# Sheet1.net
KiCad netlist of a schematic drawn in Altium Designer
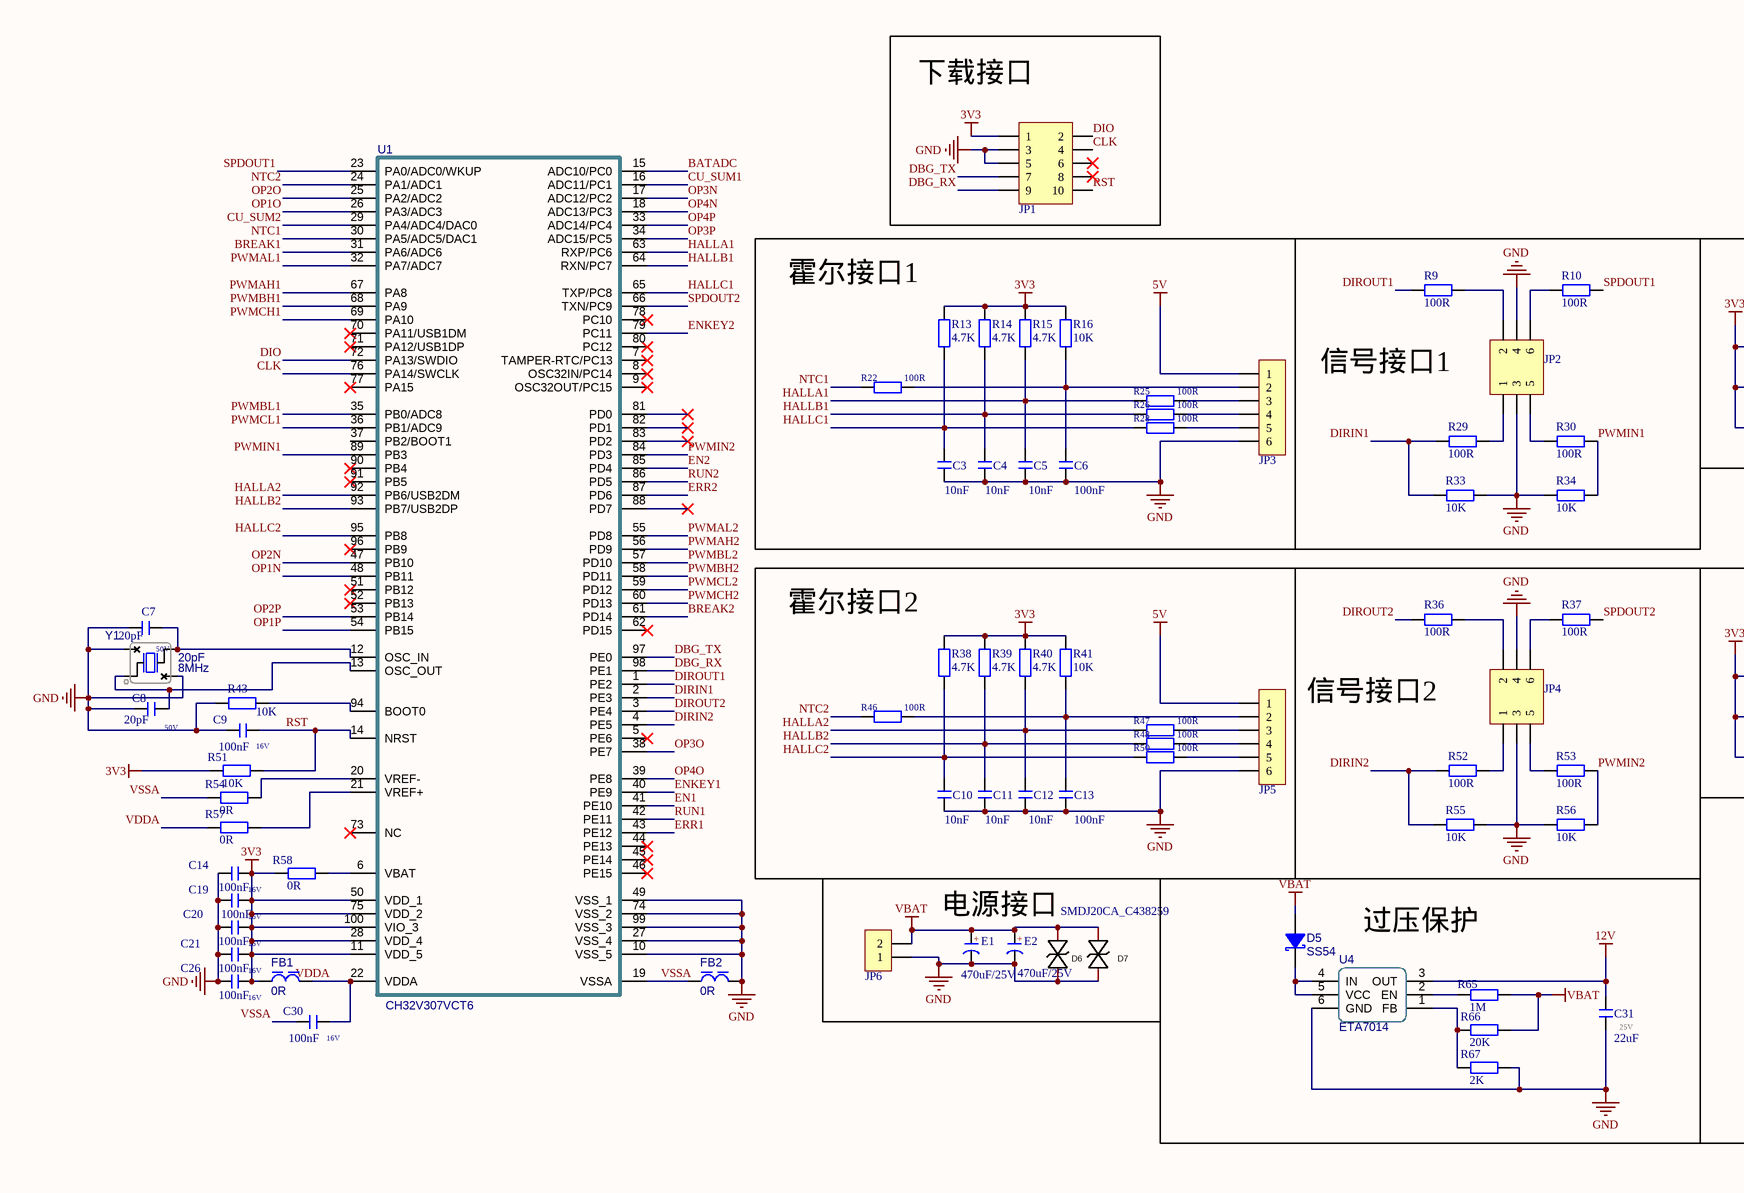
[diagram p0: Sheet1.SchDoc, top left]
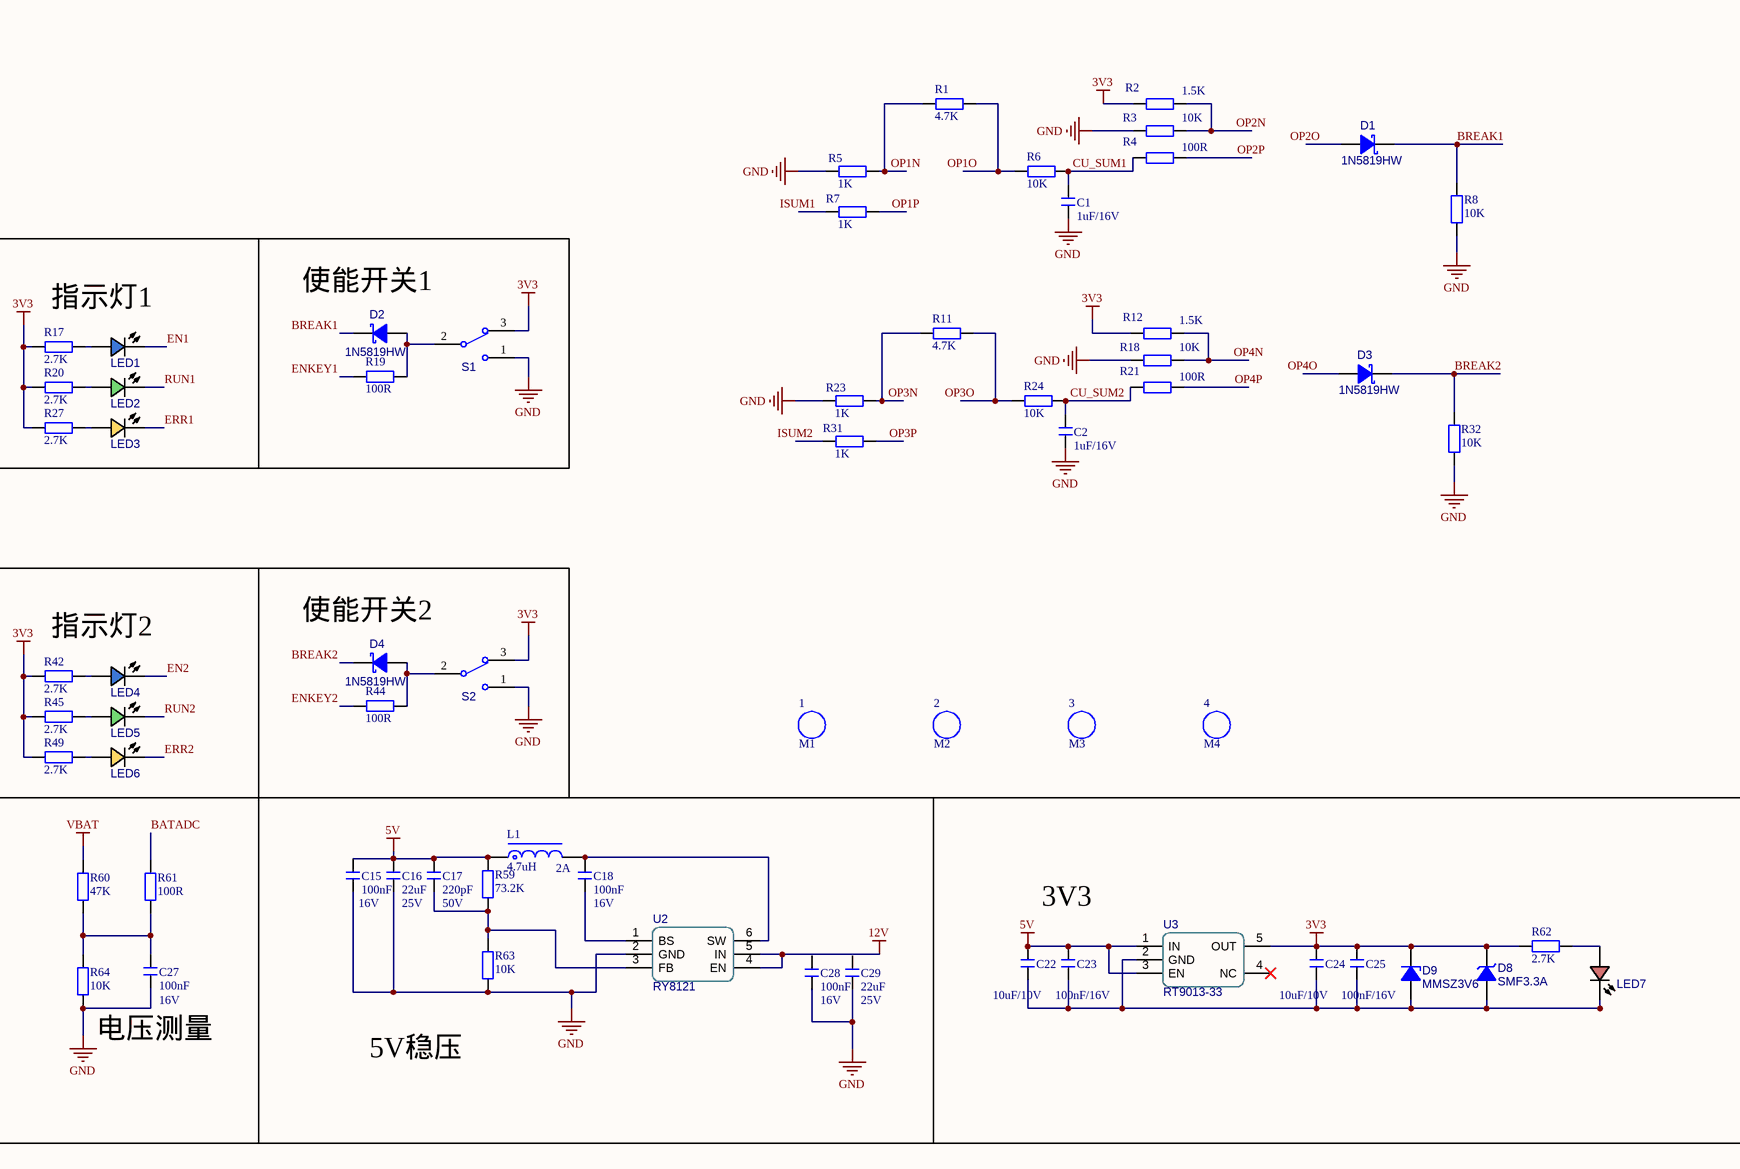
[diagram p1: Sheet1.SchDoc, top right]
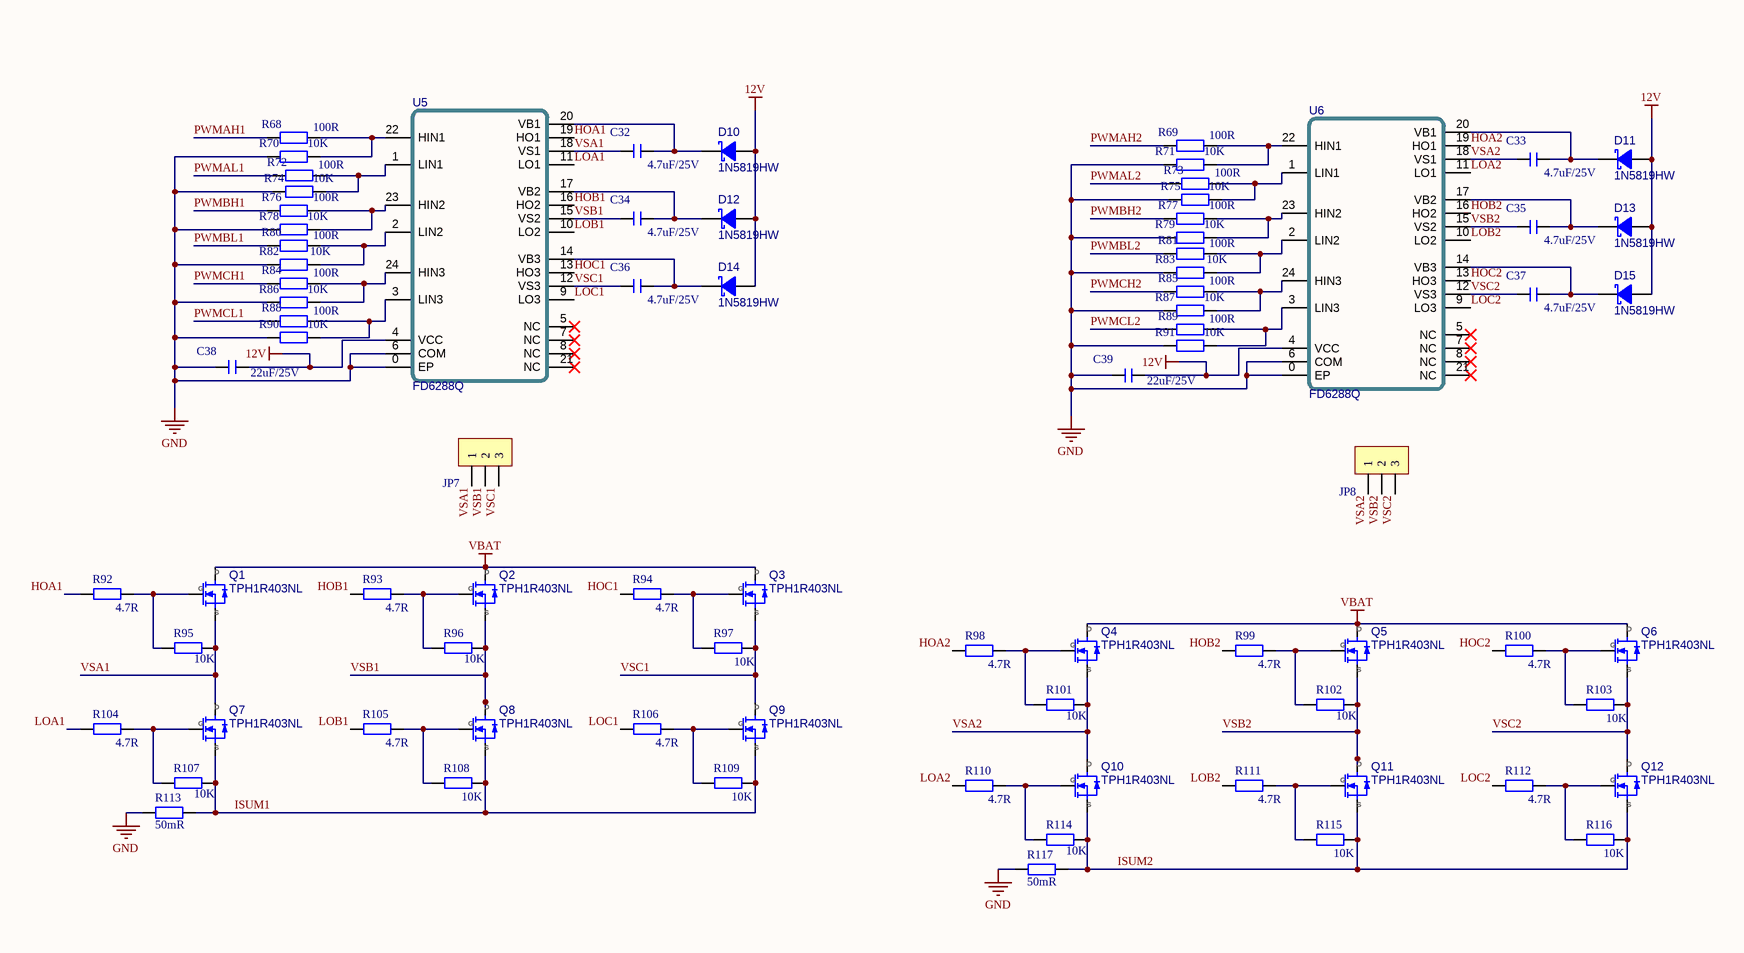
[diagram p2: Sheet1.SchDoc, bottom left]

(export (version "E")
  (design (tool "Eeschema 10.0.6"))
  (components
    (comp (ref "1")
      (value "M1")
      (footprint "M3 125X200")
      (description "铜柱孔")
      (fields (field (name "版权归属") "源创客"))
      (libsource (lib "15.1 - 未分类器件") (part "M3"))
    )
    (comp (ref "2")
      (value "M2")
      (footprint "M3 125X200")
      (description "铜柱孔")
      (fields (field (name "版权归属") "源创客"))
      (libsource (lib "15.1 - 未分类器件") (part "M3"))
    )
    (comp (ref "3")
      (value "M3")
      (footprint "M3 125X200")
      (description "铜柱孔")
      (fields (field (name "版权归属") "源创客"))
      (libsource (lib "15.1 - 未分类器件") (part "M3"))
    )
    (comp (ref "4")
      (value "M4")
      (footprint "M3 125X200")
      (description "铜柱孔")
      (fields (field (name "版权归属") "源创客"))
      (libsource (lib "15.1 - 未分类器件") (part "M3"))
    )
    (comp (ref "C1")
      (value "1uF/16V")
      (footprint "C 0603_L")
      (description "无极性贴片电容")
      (fields (field (name "版权归属") "源创客"))
      (libsource (lib "3.1   - 电阻-电容-电感") (part "C"))
    )
    (comp (ref "C2")
      (value "1uF/16V")
      (footprint "C 0603_L")
      (description "无极性贴片电容")
      (fields (field (name "版权归属") "源创客"))
      (libsource (lib "3.1   - 电阻-电容-电感") (part "C"))
    )
    (comp (ref "C3")
      (value "10nF")
      (footprint "C 0402_L")
      (description "无极性贴片电容")
      (fields (field (name "版权归属") "源创客"))
      (libsource (lib "3.1   - 电阻-电容-电感") (part "C"))
    )
    (comp (ref "C4")
      (value "10nF")
      (footprint "C 0402_L")
      (description "无极性贴片电容")
      (fields (field (name "版权归属") "源创客"))
      (libsource (lib "3.1   - 电阻-电容-电感") (part "C"))
    )
    (comp (ref "C5")
      (value "10nF")
      (footprint "C 0402_L")
      (description "无极性贴片电容")
      (fields (field (name "版权归属") "源创客"))
      (libsource (lib "3.1   - 电阻-电容-电感") (part "C"))
    )
    (comp (ref "C6")
      (value "100nF")
      (footprint "C 0402_L")
      (description "无极性贴片电容")
      (fields (field (name "版权归属") "源创客"))
      (libsource (lib "3.1   - 电阻-电容-电感") (part "C"))
    )
    (comp (ref "C7")
      (value "20pF")
      (footprint "C 0402_L")
      (description "无极性贴片电容")
      (fields (field (name "电压") "50V") (field (name "版权归属") "源创客"))
      (libsource (lib "3.1   - 电阻-电容-电感") (part "C"))
    )
    (comp (ref "C8")
      (value "20pF")
      (footprint "C 0402_L")
      (description "无极性贴片电容")
      (fields (field (name "电压") "50V") (field (name "版权归属") "源创客"))
      (libsource (lib "3.1   - 电阻-电容-电感") (part "C"))
    )
    (comp (ref "C9")
      (value "100nF")
      (footprint "C 0402_L")
      (description "无极性贴片电容")
      (fields (field (name "电压") "16V") (field (name "版权归属") "源创客"))
      (libsource (lib "3.1   - 电阻-电容-电感") (part "C"))
    )
    (comp (ref "C10")
      (value "10nF")
      (footprint "C 0402_L")
      (description "无极性贴片电容")
      (fields (field (name "版权归属") "源创客"))
      (libsource (lib "3.1   - 电阻-电容-电感") (part "C"))
    )
    (comp (ref "C11")
      (value "10nF")
      (footprint "C 0402_L")
      (description "无极性贴片电容")
      (fields (field (name "版权归属") "源创客"))
      (libsource (lib "3.1   - 电阻-电容-电感") (part "C"))
    )
    (comp (ref "C12")
      (value "10nF")
      (footprint "C 0402_L")
      (description "无极性贴片电容")
      (fields (field (name "版权归属") "源创客"))
      (libsource (lib "3.1   - 电阻-电容-电感") (part "C"))
    )
    (comp (ref "C13")
      (value "100nF")
      (footprint "C 0402_L")
      (description "无极性贴片电容")
      (fields (field (name "版权归属") "源创客"))
      (libsource (lib "3.1   - 电阻-电容-电感") (part "C"))
    )
    (comp (ref "C14")
      (value "100nF")
      (footprint "C 0402_L")
      (description "无极性贴片电容")
      (fields (field (name "电压") "16V") (field (name "版权归属") "源创客"))
      (libsource (lib "3.1   - 电阻-电容-电感") (part "C"))
    )
    (comp (ref "C15")
      (value "100nF")
      (footprint "C 0402_L")
      (description "无极性贴片电容")
      (fields (field (name "V") "16V") (field (name "版权归属") "源创客"))
      (libsource (lib "3.1   - 电阻-电容-电感") (part "C"))
    )
    (comp (ref "C16")
      (value "22uF")
      (footprint "C 0805_L")
      (description "无极性贴片电容")
      (fields (field (name "V") "25V") (field (name "版权归属") "源创客"))
      (libsource (lib "3.1   - 电阻-电容-电感") (part "C"))
    )
    (comp (ref "C17")
      (value "220pF")
      (footprint "C 0402_L")
      (description "无极性贴片电容")
      (fields (field (name "V") "50V") (field (name "版权归属") "源创客"))
      (libsource (lib "3.1   - 电阻-电容-电感") (part "C"))
    )
    (comp (ref "C18")
      (value "100nF")
      (footprint "C 0402_L")
      (description "无极性贴片电容")
      (fields (field (name "V") "16V") (field (name "版权归属") "源创客"))
      (libsource (lib "3.1   - 电阻-电容-电感") (part "C"))
    )
    (comp (ref "C19")
      (value "100nF")
      (footprint "C 0402_L")
      (description "无极性贴片电容")
      (fields (field (name "电压") "16V") (field (name "版权归属") "源创客"))
      (libsource (lib "3.1   - 电阻-电容-电感") (part "C"))
    )
    (comp (ref "C20")
      (value "100nF")
      (footprint "C 0402_L")
      (description "无极性贴片电容")
      (fields (field (name "电压") "16V") (field (name "版权归属") "源创客"))
      (libsource (lib "3.1   - 电阻-电容-电感") (part "C"))
    )
    (comp (ref "C21")
      (value "100nF")
      (footprint "C 0402_L")
      (description "无极性贴片电容")
      (fields (field (name "电压") "16V") (field (name "版权归属") "源创客"))
      (libsource (lib "3.1   - 电阻-电容-电感") (part "C"))
    )
    (comp (ref "C22")
      (value "10uF/10V")
      (footprint "C 0603_L")
      (description "无极性贴片电容")
      (fields (field (name "版权归属") "源创客"))
      (libsource (lib "3.1   - 电阻-电容-电感") (part "C"))
    )
    (comp (ref "C23")
      (value "100nF/16V")
      (footprint "C 0402_L")
      (description "无极性贴片电容")
      (fields (field (name "版权归属") "源创客"))
      (libsource (lib "3.1   - 电阻-电容-电感") (part "C"))
    )
    (comp (ref "C24")
      (value "10uF/10V")
      (footprint "C 0603_L")
      (description "无极性贴片电容")
      (fields (field (name "版权归属") "源创客"))
      (libsource (lib "3.1   - 电阻-电容-电感") (part "C"))
    )
    (comp (ref "C25")
      (value "100nF/16V")
      (footprint "C 0402_L")
      (description "无极性贴片电容")
      (fields (field (name "版权归属") "源创客"))
      (libsource (lib "3.1   - 电阻-电容-电感") (part "C"))
    )
    (comp (ref "C26")
      (value "100nF")
      (footprint "C 0402_L")
      (description "无极性贴片电容")
      (fields (field (name "电压") "16V") (field (name "版权归属") "源创客"))
      (libsource (lib "3.1   - 电阻-电容-电感") (part "C"))
    )
    (comp (ref "C27")
      (value "100nF")
      (footprint "C 0402_L")
      (description "无极性贴片电容")
      (fields (field (name "V") "16V") (field (name "版权归属") "源创客"))
      (libsource (lib "3.1   - 电阻-电容-电感") (part "C"))
    )
    (comp (ref "C28")
      (value "100nF")
      (footprint "C 0402_L")
      (description "无极性贴片电容")
      (fields (field (name "V") "16V") (field (name "版权归属") "源创客"))
      (libsource (lib "3.1   - 电阻-电容-电感") (part "C"))
    )
    (comp (ref "C29")
      (value "22uF")
      (footprint "C 0805_L")
      (description "无极性贴片电容")
      (fields (field (name "V") "25V") (field (name "版权归属") "源创客"))
      (libsource (lib "3.1   - 电阻-电容-电感") (part "C"))
    )
    (comp (ref "C30")
      (value "100nF")
      (footprint "C 0402_M")
      (description "无极性贴片电容")
      (fields (field (name "电压") "16V") (field (name "版权归属") "源创客"))
      (libsource (lib "3.1   - 电阻-电容-电感") (part "C"))
    )
    (comp (ref "C31")
      (value "22uF")
      (footprint "C 0805_L")
      (description "无极性贴片电容")
      (fields (field (name "V") "25V") (field (name "版权归属") "源创客"))
      (libsource (lib "3.1   - 电阻-电容-电感") (part "C"))
    )
    (comp (ref "C32")
      (value "4.7uF/25V")
      (footprint "C 0805_L")
      (description "无极性贴片电容")
      (fields (field (name "版权归属") "源创客"))
      (libsource (lib "3.1   - 电阻-电容-电感") (part "C"))
    )
    (comp (ref "C33")
      (value "4.7uF/25V")
      (footprint "C 0805_L")
      (description "无极性贴片电容")
      (fields (field (name "版权归属") "源创客"))
      (libsource (lib "3.1   - 电阻-电容-电感") (part "C"))
    )
    (comp (ref "C34")
      (value "4.7uF/25V")
      (footprint "C 0805_L")
      (description "无极性贴片电容")
      (fields (field (name "版权归属") "源创客"))
      (libsource (lib "3.1   - 电阻-电容-电感") (part "C"))
    )
    (comp (ref "C35")
      (value "4.7uF/25V")
      (footprint "C 0805_L")
      (description "无极性贴片电容")
      (fields (field (name "版权归属") "源创客"))
      (libsource (lib "3.1   - 电阻-电容-电感") (part "C"))
    )
    (comp (ref "C36")
      (value "4.7uF/25V")
      (footprint "C 0805_L")
      (description "无极性贴片电容")
      (fields (field (name "版权归属") "源创客"))
      (libsource (lib "3.1   - 电阻-电容-电感") (part "C"))
    )
    (comp (ref "C37")
      (value "4.7uF/25V")
      (footprint "C 0805_L")
      (description "无极性贴片电容")
      (fields (field (name "版权归属") "源创客"))
      (libsource (lib "3.1   - 电阻-电容-电感") (part "C"))
    )
    (comp (ref "C38")
      (value "22uF/25V")
      (footprint "C 0805_L")
      (description "无极性贴片电容")
      (fields (field (name "版权归属") "源创客"))
      (libsource (lib "3.1   - 电阻-电容-电感") (part "C"))
    )
    (comp (ref "C39")
      (value "22uF/25V")
      (footprint "C 0805_L")
      (description "无极性贴片电容")
      (fields (field (name "版权归属") "源创客"))
      (libsource (lib "3.1   - 电阻-电容-电感") (part "C"))
    )
    (comp (ref "D1")
      (value "1N5819HW")
      (footprint "SOD-123-L")
      (description "1N5819HW 肖特基二极管")
      (libsource (lib "无刷驱动_CH32V307_V1.0") (part "1N5819HW"))
    )
    (comp (ref "D2")
      (value "1N5819HW")
      (footprint "SOD-123-L")
      (description "1N5819HW 肖特基二极管")
      (libsource (lib "无刷驱动_CH32V307_V1.0") (part "1N5819HW"))
    )
    (comp (ref "D3")
      (value "1N5819HW")
      (footprint "SOD-123-L")
      (description "1N5819HW 肖特基二极管")
      (libsource (lib "无刷驱动_CH32V307_V1.0") (part "1N5819HW"))
    )
    (comp (ref "D4")
      (value "1N5819HW")
      (footprint "SOD-123-L")
      (description "1N5819HW 肖特基二极管")
      (libsource (lib "无刷驱动_CH32V307_V1.0") (part "1N5819HW"))
    )
    (comp (ref "D5")
      (value "SS54")
      (footprint "SMA-L[DO-214AC]")
      (description "SS54 肖特基二极管")
      (libsource (lib "无刷驱动_CH32V307_V1.0") (part "SS54"))
    )
    (comp (ref "D6")
      (value "SMDJ20CA_C438259")
      (footprint "SMC_L6.9-W5.9-LS7.9-BI")
      (fields (field (name "DESIGNER") "U?"))
      (libsource (lib "SMDJ20CA_C4382591_SMDJ20CA_C438259") (part "SMDJ20CA_C438259"))
    )
    (comp (ref "D7")
      (value "SMDJ20CA_C438259")
      (footprint "SMC_L6.9-W5.9-LS7.9-BI")
      (fields (field (name "DESIGNER") "U?"))
      (libsource (lib "SMDJ20CA_C4382591_SMDJ20CA_C438259") (part "SMDJ20CA_C438259"))
    )
    (comp (ref "D8")
      (value "SMF3.3A")
      (footprint "SOD-123-L")
      (description "TRANSIENT VOLTAGE  SUPPRESSOR DIODE")
      (fields (field (name "PUBLISHER") "Altium Limited"))
      (libsource (lib "无刷驱动_CH32V307_V1.0") (part "Diode TVS Uni-Dir"))
    )
    (comp (ref "D9")
      (value "MMSZ3V6")
      (footprint "SOD-123-L")
      (description "稳压二极管 齐纳二极管  Zener Diode")
      (fields (field (name "PUBLISHER") "Altium Limited"))
      (libsource (lib "无刷驱动_CH32V307_V1.0") (part "Diode Zen"))
    )
    (comp (ref "D10")
      (value "1N5819HW")
      (footprint "SOD-123-L")
      (description "1N5819HW 肖特基二极管")
      (libsource (lib "无刷驱动_CH32V307_V1.0") (part "1N5819HW"))
    )
    (comp (ref "D11")
      (value "1N5819HW")
      (footprint "SOD-123-L")
      (description "1N5819HW 肖特基二极管")
      (libsource (lib "无刷驱动_CH32V307_V1.0") (part "1N5819HW"))
    )
    (comp (ref "D12")
      (value "1N5819HW")
      (footprint "SOD-123-L")
      (description "1N5819HW 肖特基二极管")
      (libsource (lib "无刷驱动_CH32V307_V1.0") (part "1N5819HW"))
    )
    (comp (ref "D13")
      (value "1N5819HW")
      (footprint "SOD-123-L")
      (description "1N5819HW 肖特基二极管")
      (libsource (lib "无刷驱动_CH32V307_V1.0") (part "1N5819HW"))
    )
    (comp (ref "D14")
      (value "1N5819HW")
      (footprint "SOD-123-L")
      (description "1N5819HW 肖特基二极管")
      (libsource (lib "无刷驱动_CH32V307_V1.0") (part "1N5819HW"))
    )
    (comp (ref "D15")
      (value "1N5819HW")
      (footprint "SOD-123-L")
      (description "1N5819HW 肖特基二极管")
      (libsource (lib "无刷驱动_CH32V307_V1.0") (part "1N5819HW"))
    )
    (comp (ref "E1")
      (value "470uF/25V")
      (footprint "CAP 5.0*10*12.5")
      (description "直插电解电容")
      (fields (field (name "版权归属") "源创客"))
      (libsource (lib "3.1   - 电阻-电容-电感") (part "C-CAP"))
    )
    (comp (ref "E2")
      (value "470uF/25V")
      (footprint "CAP 5.0*10*16")
      (description "直插电解电容")
      (fields (field (name "版权归属") "源创客"))
      (libsource (lib "3.1   - 电阻-电容-电感") (part "C-CAP"))
    )
    (comp (ref "FB1")
      (value "0R")
      (footprint "INDC1005[0402]S")
      (description "贴片磁珠")
      (fields (field (name "Comment") "0R @100MHz 500mA"))
      (libsource (lib "无刷驱动_CH32V307_V1.0") (part "FB-Chip"))
    )
    (comp (ref "FB2")
      (value "0R")
      (footprint "INDC1005[0402]S")
      (description "贴片磁珠")
      (fields (field (name "Comment") "0R @100MHz 500mA"))
      (libsource (lib "无刷驱动_CH32V307_V1.0") (part "FB-Chip"))
    )
    (comp (ref "JP1")
      (value "Header 5X2")
      (footprint "HDR2.54-WI-2x5P")
      (description "5*2P接插件")
      (fields (field (name "版权归属") "源创客"))
      (libsource (lib "4.5   - 接插件-脚距2.54") (part "Header 5X2"))
    )
    (comp (ref "JP2")
      (value "Header3X2")
      (footprint "HDR2.54-LI-2x3P")
      (description "3*2P接插件")
      (fields (field (name "版权归属") "源创客"))
      (libsource (lib "4.5   - 接插件-脚距2.54") (part "Header 3X2"))
    )
    (comp (ref "JP3")
      (value "HDR-1X6")
      (footprint "ZH1.5-WI-6P")
      (description "6P接插件")
      (fields (field (name "版权归属") "源创客"))
      (libsource (lib "4.3   - 接插件-脚距1.5") (part "Header 6"))
    )
    (comp (ref "JP4")
      (value "Header3X2")
      (footprint "HDR2.54-LI-2x3P")
      (description "3*2P接插件")
      (fields (field (name "版权归属") "源创客"))
      (libsource (lib "4.5   - 接插件-脚距2.54") (part "Header 3X2"))
    )
    (comp (ref "JP5")
      (value "HDR-1X6")
      (footprint "ZH1.5-WI-6P")
      (description "6P接插件")
      (fields (field (name "版权归属") "源创客"))
      (libsource (lib "4.3   - 接插件-脚距1.5") (part "Header 6"))
    )
    (comp (ref "JP6")
      (value "HDR-1X2")
      (footprint "KF350-2P")
      (description "2P接插件")
      (fields (field (name "版权归属") "源创客"))
      (libsource (lib "4.6   - 接插件-脚距3.5") (part "Header 2"))
    )
    (comp (ref "JP7")
      (value "HDR-1X3")
      (footprint "KF350-3P")
      (description "3P接插件")
      (fields (field (name "版权归属") "源创客"))
      (libsource (lib "4.6   - 接插件-脚距3.5") (part "Header 3"))
    )
    (comp (ref "JP8")
      (value "HDR-1X3")
      (footprint "KF350-3P")
      (description "3P接插件")
      (fields (field (name "版权归属") "源创客"))
      (libsource (lib "4.6   - 接插件-脚距3.5") (part "Header 3"))
    )
    (comp (ref "L1")
      (value "4.7uH")
      (footprint "CD31")
      (description "贴片功率电感")
      (fields (field (name "A") "2A") (field (name "版权归属") "源创客"))
      (libsource (lib "3.1   - 电阻-电容-电感") (part "L-CD"))
    )
    (comp (ref "LED1")
      (value "蓝色贴片LED")
      (footprint "LEDC1608(0603)-L")
      (fields (field (name "PUBLISHER") "Altium Limited"))
      (libsource (lib "无刷驱动_CH32V307_V1.0") (part "LED Chip Blue"))
    )
    (comp (ref "LED2")
      (value "翠绿贴片LED")
      (footprint "LEDC1608(0603)-L")
      (fields (field (name "PUBLISHER") "Altium Limited"))
      (libsource (lib "无刷驱动_CH32V307_V1.0") (part "LED Chip Green"))
    )
    (comp (ref "LED3")
      (value "黄色贴片LED")
      (footprint "LEDC1608(0603)-L")
      (fields (field (name "PUBLISHER") "Altium Limited"))
      (libsource (lib "无刷驱动_CH32V307_V1.0") (part "LED Chip Yellow"))
    )
    (comp (ref "LED4")
      (value "蓝色贴片LED")
      (footprint "LEDC1608(0603)-L")
      (fields (field (name "PUBLISHER") "Altium Limited"))
      (libsource (lib "无刷驱动_CH32V307_V1.0") (part "LED Chip Blue"))
    )
    (comp (ref "LED5")
      (value "翠绿贴片LED")
      (footprint "LEDC1608(0603)-L")
      (fields (field (name "PUBLISHER") "Altium Limited"))
      (libsource (lib "无刷驱动_CH32V307_V1.0") (part "LED Chip Green"))
    )
    (comp (ref "LED6")
      (value "黄色贴片LED")
      (footprint "LEDC1608(0603)-L")
      (fields (field (name "PUBLISHER") "Altium Limited"))
      (libsource (lib "无刷驱动_CH32V307_V1.0") (part "LED Chip Yellow"))
    )
    (comp (ref "LED7")
      (value "红色贴片LED")
      (footprint "LEDC1608(0603)-L")
      (fields (field (name "PUBLISHER") "Altium Limited"))
      (libsource (lib "无刷驱动_CH32V307_V1.0") (part "LED Chip Red"))
    )
    (comp (ref "Q1")
      (value "TPH1R403NL")
      (footprint "DFN5x6")
      (description "东芝 N沟 MOS")
      (libsource (lib "无刷驱动_CH32V307_V1.0") (part "TPH1R403NL"))
    )
    (comp (ref "Q2")
      (value "TPH1R403NL")
      (footprint "DFN5x6")
      (description "东芝 N沟 MOS")
      (libsource (lib "无刷驱动_CH32V307_V1.0") (part "TPH1R403NL"))
    )
    (comp (ref "Q3")
      (value "TPH1R403NL")
      (footprint "DFN5x6")
      (description "东芝 N沟 MOS")
      (libsource (lib "无刷驱动_CH32V307_V1.0") (part "TPH1R403NL"))
    )
    (comp (ref "Q4")
      (value "TPH1R403NL")
      (footprint "DFN5x6")
      (description "东芝 N沟 MOS")
      (libsource (lib "无刷驱动_CH32V307_V1.0") (part "TPH1R403NL"))
    )
    (comp (ref "Q5")
      (value "TPH1R403NL")
      (footprint "DFN5x6")
      (description "东芝 N沟 MOS")
      (libsource (lib "无刷驱动_CH32V307_V1.0") (part "TPH1R403NL"))
    )
    (comp (ref "Q6")
      (value "TPH1R403NL")
      (footprint "DFN5x6")
      (description "东芝 N沟 MOS")
      (libsource (lib "无刷驱动_CH32V307_V1.0") (part "TPH1R403NL"))
    )
    (comp (ref "Q7")
      (value "TPH1R403NL")
      (footprint "DFN5x6")
      (description "东芝 N沟 MOS")
      (libsource (lib "无刷驱动_CH32V307_V1.0") (part "TPH1R403NL"))
    )
    (comp (ref "Q8")
      (value "TPH1R403NL")
      (footprint "DFN5x6")
      (description "东芝 N沟 MOS")
      (libsource (lib "无刷驱动_CH32V307_V1.0") (part "TPH1R403NL"))
    )
    (comp (ref "Q9")
      (value "TPH1R403NL")
      (footprint "DFN5x6")
      (description "东芝 N沟 MOS")
      (libsource (lib "无刷驱动_CH32V307_V1.0") (part "TPH1R403NL"))
    )
    (comp (ref "Q10")
      (value "TPH1R403NL")
      (footprint "DFN5x6")
      (description "东芝 N沟 MOS")
      (libsource (lib "无刷驱动_CH32V307_V1.0") (part "TPH1R403NL"))
    )
    (comp (ref "Q11")
      (value "TPH1R403NL")
      (footprint "DFN5x6")
      (description "东芝 N沟 MOS")
      (libsource (lib "无刷驱动_CH32V307_V1.0") (part "TPH1R403NL"))
    )
    (comp (ref "Q12")
      (value "TPH1R403NL")
      (footprint "DFN5x6")
      (description "东芝 N沟 MOS")
      (libsource (lib "无刷驱动_CH32V307_V1.0") (part "TPH1R403NL"))
    )
    (comp (ref "R1")
      (value "4.7K")
      (footprint "R 0603_L")
      (description "贴片电阻")
      (fields (field (name "版权归属") "源创客"))
      (libsource (lib "3.1   - 电阻-电容-电感") (part "R"))
    )
    (comp (ref "R2")
      (value "1.5K")
      (footprint "R 0603_L")
      (description "贴片电阻")
      (fields (field (name "版权归属") "源创客"))
      (libsource (lib "3.1   - 电阻-电容-电感") (part "R"))
    )
    (comp (ref "R3")
      (value "10K")
      (footprint "R 0603_L")
      (description "贴片电阻")
      (fields (field (name "版权归属") "源创客"))
      (libsource (lib "3.1   - 电阻-电容-电感") (part "R"))
    )
    (comp (ref "R4")
      (value "100R")
      (footprint "R 0603_L")
      (description "贴片电阻")
      (fields (field (name "版权归属") "源创客"))
      (libsource (lib "3.1   - 电阻-电容-电感") (part "R"))
    )
    (comp (ref "R5")
      (value "1K")
      (footprint "R 0603_L")
      (description "贴片电阻")
      (fields (field (name "版权归属") "源创客"))
      (libsource (lib "3.1   - 电阻-电容-电感") (part "R"))
    )
    (comp (ref "R6")
      (value "10K")
      (footprint "R 0603_L")
      (description "贴片电阻")
      (fields (field (name "版权归属") "源创客"))
      (libsource (lib "3.1   - 电阻-电容-电感") (part "R"))
    )
    (comp (ref "R7")
      (value "1K")
      (footprint "R 0603_L")
      (description "贴片电阻")
      (fields (field (name "版权归属") "源创客"))
      (libsource (lib "3.1   - 电阻-电容-电感") (part "R"))
    )
    (comp (ref "R8")
      (value "10K")
      (footprint "R 0603_L")
      (description "贴片电阻")
      (fields (field (name "版权归属") "源创客"))
      (libsource (lib "3.1   - 电阻-电容-电感") (part "R"))
    )
    (comp (ref "R9")
      (value "100R")
      (footprint "R 0603_L")
      (description "贴片电阻")
      (fields (field (name "版权归属") "源创客"))
      (libsource (lib "3.1   - 电阻-电容-电感") (part "R"))
    )
    (comp (ref "R10")
      (value "100R")
      (footprint "R 0603_L")
      (description "贴片电阻")
      (fields (field (name "版权归属") "源创客"))
      (libsource (lib "3.1   - 电阻-电容-电感") (part "R"))
    )
    (comp (ref "R11")
      (value "4.7K")
      (footprint "R 0603_L")
      (description "贴片电阻")
      (fields (field (name "版权归属") "源创客"))
      (libsource (lib "3.1   - 电阻-电容-电感") (part "R"))
    )
    (comp (ref "R12")
      (value "1.5K")
      (footprint "R 0603_L")
      (description "贴片电阻")
      (fields (field (name "版权归属") "源创客"))
      (libsource (lib "3.1   - 电阻-电容-电感") (part "R"))
    )
    (comp (ref "R13")
      (value "4.7K")
      (footprint "R 0603_L")
      (description "贴片电阻")
      (fields (field (name "版权归属") "源创客"))
      (libsource (lib "3.1   - 电阻-电容-电感") (part "R"))
    )
    (comp (ref "R14")
      (value "4.7K")
      (footprint "R 0603_L")
      (description "贴片电阻")
      (fields (field (name "版权归属") "源创客"))
      (libsource (lib "3.1   - 电阻-电容-电感") (part "R"))
    )
    (comp (ref "R15")
      (value "4.7K")
      (footprint "R 0603_L")
      (description "贴片电阻")
      (fields (field (name "版权归属") "源创客"))
      (libsource (lib "3.1   - 电阻-电容-电感") (part "R"))
    )
    (comp (ref "R16")
      (value "10K")
      (footprint "R 0603_L")
      (description "贴片电阻")
      (fields (field (name "版权归属") "源创客"))
      (libsource (lib "3.1   - 电阻-电容-电感") (part "R"))
    )
    (comp (ref "R17")
      (value "2.7K")
      (footprint "R 0603_L")
      (description "贴片电阻")
      (fields (field (name "版权归属") "源创客"))
      (libsource (lib "3.1   - 电阻-电容-电感") (part "R"))
    )
    (comp (ref "R18")
      (value "10K")
      (footprint "R 0603_L")
      (description "贴片电阻")
      (fields (field (name "版权归属") "源创客"))
      (libsource (lib "3.1   - 电阻-电容-电感") (part "R"))
    )
    (comp (ref "R19")
      (value "100R")
      (footprint "R 0603_L")
      (description "贴片电阻")
      (fields (field (name "版权归属") "源创客"))
      (libsource (lib "3.1   - 电阻-电容-电感") (part "R"))
    )
    (comp (ref "R20")
      (value "2.7K")
      (footprint "R 0603_L")
      (description "贴片电阻")
      (fields (field (name "版权归属") "源创客"))
      (libsource (lib "3.1   - 电阻-电容-电感") (part "R"))
    )
    (comp (ref "R21")
      (value "100R")
      (footprint "R 0603_L")
      (description "贴片电阻")
      (fields (field (name "版权归属") "源创客"))
      (libsource (lib "3.1   - 电阻-电容-电感") (part "R"))
    )
    (comp (ref "R22")
      (value "100R")
      (footprint "R 0603_L")
      (description "贴片电阻")
      (fields (field (name "版权归属") "源创客"))
      (libsource (lib "3.1   - 电阻-电容-电感") (part "R"))
    )
    (comp (ref "R23")
      (value "1K")
      (footprint "R 0603_L")
      (description "贴片电阻")
      (fields (field (name "版权归属") "源创客"))
      (libsource (lib "3.1   - 电阻-电容-电感") (part "R"))
    )
    (comp (ref "R24")
      (value "10K")
      (footprint "R 0603_L")
      (description "贴片电阻")
      (fields (field (name "版权归属") "源创客"))
      (libsource (lib "3.1   - 电阻-电容-电感") (part "R"))
    )
    (comp (ref "R25")
      (value "100R")
      (footprint "R 0603_L")
      (description "贴片电阻")
      (fields (field (name "版权归属") "源创客"))
      (libsource (lib "3.1   - 电阻-电容-电感") (part "R"))
    )
    (comp (ref "R26")
      (value "100R")
      (footprint "R 0603_L")
      (description "贴片电阻")
      (fields (field (name "版权归属") "源创客"))
      (libsource (lib "3.1   - 电阻-电容-电感") (part "R"))
    )
    (comp (ref "R27")
      (value "2.7K")
      (footprint "R 0603_L")
      (description "贴片电阻")
      (fields (field (name "版权归属") "源创客"))
      (libsource (lib "3.1   - 电阻-电容-电感") (part "R"))
    )
    (comp (ref "R28")
      (value "100R")
      (footprint "R 0603_L")
      (description "贴片电阻")
      (fields (field (name "版权归属") "源创客"))
      (libsource (lib "3.1   - 电阻-电容-电感") (part "R"))
    )
    (comp (ref "R29")
      (value "100R")
      (footprint "R 0603_L")
      (description "贴片电阻")
      (fields (field (name "版权归属") "源创客"))
      (libsource (lib "3.1   - 电阻-电容-电感") (part "R"))
    )
    (comp (ref "R30")
      (value "100R")
      (footprint "R 0603_L")
      (description "贴片电阻")
      (fields (field (name "版权归属") "源创客"))
      (libsource (lib "3.1   - 电阻-电容-电感") (part "R"))
    )
    (comp (ref "R31")
      (value "1K")
      (footprint "R 0603_L")
      (description "贴片电阻")
      (fields (field (name "版权归属") "源创客"))
      (libsource (lib "3.1   - 电阻-电容-电感") (part "R"))
    )
    (comp (ref "R32")
      (value "10K")
      (footprint "R 0603_L")
      (description "贴片电阻")
      (fields (field (name "版权归属") "源创客"))
      (libsource (lib "3.1   - 电阻-电容-电感") (part "R"))
    )
    (comp (ref "R33")
      (value "10K")
      (footprint "R 0603_L")
      (description "贴片电阻")
      (fields (field (name "版权归属") "源创客"))
      (libsource (lib "3.1   - 电阻-电容-电感") (part "R"))
    )
    (comp (ref "R34")
      (value "10K")
      (footprint "R 0603_L")
      (description "贴片电阻")
      (fields (field (name "版权归属") "源创客"))
      (libsource (lib "3.1   - 电阻-电容-电感") (part "R"))
    )
    (comp (ref "R36")
      (value "100R")
      (footprint "R 0603_L")
      (description "贴片电阻")
      (fields (field (name "版权归属") "源创客"))
      (libsource (lib "3.1   - 电阻-电容-电感") (part "R"))
    )
    (comp (ref "R37")
      (value "100R")
      (footprint "R 0603_L")
      (description "贴片电阻")
      (fields (field (name "版权归属") "源创客"))
      (libsource (lib "3.1   - 电阻-电容-电感") (part "R"))
    )
    (comp (ref "R38")
      (value "4.7K")
      (footprint "R 0603_L")
      (description "贴片电阻")
      (fields (field (name "版权归属") "源创客"))
      (libsource (lib "3.1   - 电阻-电容-电感") (part "R"))
    )
    (comp (ref "R39")
      (value "4.7K")
      (footprint "R 0603_L")
      (description "贴片电阻")
      (fields (field (name "版权归属") "源创客"))
      (libsource (lib "3.1   - 电阻-电容-电感") (part "R"))
    )
    (comp (ref "R40")
      (value "4.7K")
      (footprint "R 0603_L")
      (description "贴片电阻")
      (fields (field (name "版权归属") "源创客"))
      (libsource (lib "3.1   - 电阻-电容-电感") (part "R"))
    )
    (comp (ref "R41")
      (value "10K")
      (footprint "R 0603_L")
      (description "贴片电阻")
      (fields (field (name "版权归属") "源创客"))
      (libsource (lib "3.1   - 电阻-电容-电感") (part "R"))
    )
    (comp (ref "R42")
      (value "2.7K")
      (footprint "R 0603_L")
      (description "贴片电阻")
      (fields (field (name "版权归属") "源创客"))
      (libsource (lib "3.1   - 电阻-电容-电感") (part "R"))
    )
    (comp (ref "R43")
      (value "10K")
      (footprint "R 0805_L")
      (description "贴片电阻")
      (fields (field (name "版权归属") "源创客"))
      (libsource (lib "3.1   - 电阻-电容-电感") (part "R"))
    )
    (comp (ref "R44")
      (value "100R")
      (footprint "R 0603_L")
      (description "贴片电阻")
      (fields (field (name "版权归属") "源创客"))
      (libsource (lib "3.1   - 电阻-电容-电感") (part "R"))
    )
    (comp (ref "R45")
      (value "2.7K")
      (footprint "R 0603_L")
      (description "贴片电阻")
      (fields (field (name "版权归属") "源创客"))
      (libsource (lib "3.1   - 电阻-电容-电感") (part "R"))
    )
    (comp (ref "R46")
      (value "100R")
      (footprint "R 0603_L")
      (description "贴片电阻")
      (fields (field (name "版权归属") "源创客"))
      (libsource (lib "3.1   - 电阻-电容-电感") (part "R"))
    )
    (comp (ref "R47")
      (value "100R")
      (footprint "R 0603_L")
      (description "贴片电阻")
      (fields (field (name "版权归属") "源创客"))
      (libsource (lib "3.1   - 电阻-电容-电感") (part "R"))
    )
    (comp (ref "R48")
      (value "100R")
      (footprint "R 0603_L")
      (description "贴片电阻")
      (fields (field (name "版权归属") "源创客"))
      (libsource (lib "3.1   - 电阻-电容-电感") (part "R"))
    )
    (comp (ref "R49")
      (value "2.7K")
      (footprint "R 0603_L")
      (description "贴片电阻")
      (fields (field (name "版权归属") "源创客"))
      (libsource (lib "3.1   - 电阻-电容-电感") (part "R"))
    )
    (comp (ref "R50")
      (value "100R")
      (footprint "R 0603_L")
      (description "贴片电阻")
      (fields (field (name "版权归属") "源创客"))
      (libsource (lib "3.1   - 电阻-电容-电感") (part "R"))
    )
    (comp (ref "R51")
      (value "10K")
      (footprint "R 0603_L")
      (description "贴片电阻")
      (fields (field (name "版权归属") "源创客"))
      (libsource (lib "3.1   - 电阻-电容-电感") (part "R"))
    )
    (comp (ref "R52")
      (value "100R")
      (footprint "R 0603_L")
      (description "贴片电阻")
      (fields (field (name "版权归属") "源创客"))
      (libsource (lib "3.1   - 电阻-电容-电感") (part "R"))
    )
    (comp (ref "R53")
      (value "100R")
      (footprint "R 0603_L")
      (description "贴片电阻")
      (fields (field (name "版权归属") "源创客"))
      (libsource (lib "3.1   - 电阻-电容-电感") (part "R"))
    )
    (comp (ref "R54")
      (value "0R")
      (footprint "R 0603_L")
      (description "贴片电阻")
      (fields (field (name "版权归属") "源创客"))
      (libsource (lib "3.1   - 电阻-电容-电感") (part "R"))
    )
    (comp (ref "R55")
      (value "10K")
      (footprint "R 0603_L")
      (description "贴片电阻")
      (fields (field (name "版权归属") "源创客"))
      (libsource (lib "3.1   - 电阻-电容-电感") (part "R"))
    )
    (comp (ref "R56")
      (value "10K")
      (footprint "R 0603_L")
      (description "贴片电阻")
      (fields (field (name "版权归属") "源创客"))
      (libsource (lib "3.1   - 电阻-电容-电感") (part "R"))
    )
    (comp (ref "R57")
      (value "0R")
      (footprint "R 0603_L")
      (description "贴片电阻")
      (fields (field (name "版权归属") "源创客"))
      (libsource (lib "3.1   - 电阻-电容-电感") (part "R"))
    )
    (comp (ref "R58")
      (value "0R")
      (footprint "R 0402_L")
      (description "贴片电阻")
      (fields (field (name "版权归属") "源创客"))
      (libsource (lib "3.1   - 电阻-电容-电感") (part "R"))
    )
    (comp (ref "R59")
      (value "73.2K")
      (footprint "R 0603_L")
      (description "贴片电阻")
      (fields (field (name "版权归属") "源创客"))
      (libsource (lib "3.1   - 电阻-电容-电感") (part "R"))
    )
    (comp (ref "R60")
      (value "47K")
      (footprint "R 0603_L")
      (description "贴片电阻")
      (fields (field (name "版权归属") "源创客"))
      (libsource (lib "3.1   - 电阻-电容-电感") (part "R"))
    )
    (comp (ref "R61")
      (value "100R")
      (footprint "R 0603_L")
      (description "贴片电阻")
      (fields (field (name "版权归属") "源创客"))
      (libsource (lib "3.1   - 电阻-电容-电感") (part "R"))
    )
    (comp (ref "R62")
      (value "2.7K")
      (footprint "R 0603_L")
      (description "贴片电阻")
      (fields (field (name "版权归属") "源创客"))
      (libsource (lib "3.1   - 电阻-电容-电感") (part "R"))
    )
    (comp (ref "R63")
      (value "10K")
      (footprint "R 0603_L")
      (description "贴片电阻")
      (fields (field (name "版权归属") "源创客"))
      (libsource (lib "3.1   - 电阻-电容-电感") (part "R"))
    )
    (comp (ref "R64")
      (value "10K")
      (footprint "R 0603_L")
      (description "贴片电阻")
      (fields (field (name "版权归属") "源创客"))
      (libsource (lib "3.1   - 电阻-电容-电感") (part "R"))
    )
    (comp (ref "R65")
      (value "1M")
      (footprint "R 0603_L")
      (description "贴片电阻")
      (fields (field (name "版权归属") "源创客"))
      (libsource (lib "3.1   - 电阻-电容-电感") (part "R"))
    )
    (comp (ref "R66")
      (value "20K")
      (footprint "R 0603_L")
      (description "贴片电阻")
      (fields (field (name "版权归属") "源创客"))
      (libsource (lib "3.1   - 电阻-电容-电感") (part "R"))
    )
    (comp (ref "R67")
      (value "2K")
      (footprint "R 0603_L")
      (description "贴片电阻")
      (fields (field (name "版权归属") "源创客"))
      (libsource (lib "3.1   - 电阻-电容-电感") (part "R"))
    )
    (comp (ref "R68")
      (value "100R")
      (footprint "R 0603_L")
      (description "贴片电阻")
      (fields (field (name "版权归属") "源创客"))
      (libsource (lib "3.1   - 电阻-电容-电感") (part "R"))
    )
    (comp (ref "R69")
      (value "100R")
      (footprint "R 0603_L")
      (description "贴片电阻")
      (fields (field (name "版权归属") "源创客"))
      (libsource (lib "3.1   - 电阻-电容-电感") (part "R"))
    )
    (comp (ref "R70")
      (value "10K")
      (footprint "R 0603_L")
      (description "贴片电阻")
      (fields (field (name "版权归属") "源创客"))
      (libsource (lib "3.1   - 电阻-电容-电感") (part "R"))
    )
    (comp (ref "R71")
      (value "10K")
      (footprint "R 0603_L")
      (description "贴片电阻")
      (fields (field (name "版权归属") "源创客"))
      (libsource (lib "3.1   - 电阻-电容-电感") (part "R"))
    )
    (comp (ref "R72")
      (value "100R")
      (footprint "R 0603_L")
      (description "贴片电阻")
      (fields (field (name "版权归属") "源创客"))
      (libsource (lib "3.1   - 电阻-电容-电感") (part "R"))
    )
    (comp (ref "R73")
      (value "100R")
      (footprint "R 0603_L")
      (description "贴片电阻")
      (fields (field (name "版权归属") "源创客"))
      (libsource (lib "3.1   - 电阻-电容-电感") (part "R"))
    )
    (comp (ref "R74")
      (value "10K")
      (footprint "R 0603_L")
      (description "贴片电阻")
      (fields (field (name "版权归属") "源创客"))
      (libsource (lib "3.1   - 电阻-电容-电感") (part "R"))
    )
    (comp (ref "R75")
      (value "10K")
      (footprint "R 0603_L")
      (description "贴片电阻")
      (fields (field (name "版权归属") "源创客"))
      (libsource (lib "3.1   - 电阻-电容-电感") (part "R"))
    )
    (comp (ref "R76")
      (value "100R")
      (footprint "R 0603_L")
      (description "贴片电阻")
      (fields (field (name "版权归属") "源创客"))
      (libsource (lib "3.1   - 电阻-电容-电感") (part "R"))
    )
    (comp (ref "R77")
      (value "100R")
      (footprint "R 0603_L")
      (description "贴片电阻")
      (fields (field (name "版权归属") "源创客"))
      (libsource (lib "3.1   - 电阻-电容-电感") (part "R"))
    )
    (comp (ref "R78")
      (value "10K")
      (footprint "R 0603_L")
      (description "贴片电阻")
      (fields (field (name "版权归属") "源创客"))
      (libsource (lib "3.1   - 电阻-电容-电感") (part "R"))
    )
    (comp (ref "R79")
      (value "10K")
      (footprint "R 0603_L")
      (description "贴片电阻")
      (fields (field (name "版权归属") "源创客"))
      (libsource (lib "3.1   - 电阻-电容-电感") (part "R"))
    )
    (comp (ref "R80")
      (value "100R")
      (footprint "R 0603_L")
      (description "贴片电阻")
      (fields (field (name "版权归属") "源创客"))
      (libsource (lib "3.1   - 电阻-电容-电感") (part "R"))
    )
    (comp (ref "R81")
      (value "100R")
      (footprint "R 0603_L")
      (description "贴片电阻")
      (fields (field (name "版权归属") "源创客"))
      (libsource (lib "3.1   - 电阻-电容-电感") (part "R"))
    )
    (comp (ref "R82")
      (value "10K")
      (footprint "R 0603_L")
      (description "贴片电阻")
      (fields (field (name "版权归属") "源创客"))
      (libsource (lib "3.1   - 电阻-电容-电感") (part "R"))
    )
    (comp (ref "R83")
      (value "10K")
      (footprint "R 0603_L")
      (description "贴片电阻")
      (fields (field (name "版权归属") "源创客"))
      (libsource (lib "3.1   - 电阻-电容-电感") (part "R"))
    )
    (comp (ref "R84")
      (value "100R")
      (footprint "R 0603_L")
      (description "贴片电阻")
      (fields (field (name "版权归属") "源创客"))
      (libsource (lib "3.1   - 电阻-电容-电感") (part "R"))
    )
    (comp (ref "R85")
      (value "100R")
      (footprint "R 0603_L")
      (description "贴片电阻")
      (fields (field (name "版权归属") "源创客"))
      (libsource (lib "3.1   - 电阻-电容-电感") (part "R"))
    )
    (comp (ref "R86")
      (value "10K")
      (footprint "R 0603_L")
      (description "贴片电阻")
      (fields (field (name "版权归属") "源创客"))
      (libsource (lib "3.1   - 电阻-电容-电感") (part "R"))
    )
    (comp (ref "R87")
      (value "10K")
      (footprint "R 0603_L")
      (description "贴片电阻")
      (fields (field (name "版权归属") "源创客"))
      (libsource (lib "3.1   - 电阻-电容-电感") (part "R"))
    )
    (comp (ref "R88")
      (value "100R")
      (footprint "R 0603_L")
      (description "贴片电阻")
      (fields (field (name "版权归属") "源创客"))
      (libsource (lib "3.1   - 电阻-电容-电感") (part "R"))
    )
    (comp (ref "R89")
      (value "100R")
      (footprint "R 0603_L")
      (description "贴片电阻")
      (fields (field (name "版权归属") "源创客"))
      (libsource (lib "3.1   - 电阻-电容-电感") (part "R"))
    )
    (comp (ref "R90")
      (value "10K")
      (footprint "R 0603_L")
      (description "贴片电阻")
      (fields (field (name "版权归属") "源创客"))
      (libsource (lib "3.1   - 电阻-电容-电感") (part "R"))
    )
    (comp (ref "R91")
      (value "10K")
      (footprint "R 0603_L")
      (description "贴片电阻")
      (fields (field (name "版权归属") "源创客"))
      (libsource (lib "3.1   - 电阻-电容-电感") (part "R"))
    )
    (comp (ref "R92")
      (value "4.7R")
      (footprint "R 0603_L")
      (description "贴片电阻")
      (fields (field (name "版权归属") "源创客"))
      (libsource (lib "3.1   - 电阻-电容-电感") (part "R"))
    )
    (comp (ref "R93")
      (value "4.7R")
      (footprint "R 0603_L")
      (description "贴片电阻")
      (fields (field (name "版权归属") "源创客"))
      (libsource (lib "3.1   - 电阻-电容-电感") (part "R"))
    )
    (comp (ref "R94")
      (value "4.7R")
      (footprint "R 0603_L")
      (description "贴片电阻")
      (fields (field (name "版权归属") "源创客"))
      (libsource (lib "3.1   - 电阻-电容-电感") (part "R"))
    )
    (comp (ref "R95")
      (value "10K")
      (footprint "R 0603_L")
      (description "贴片电阻")
      (fields (field (name "版权归属") "源创客"))
      (libsource (lib "3.1   - 电阻-电容-电感") (part "R"))
    )
    (comp (ref "R96")
      (value "10K")
      (footprint "R 0603_L")
      (description "贴片电阻")
      (fields (field (name "版权归属") "源创客"))
      (libsource (lib "3.1   - 电阻-电容-电感") (part "R"))
    )
    (comp (ref "R97")
      (value "10K")
      (footprint "R 0603_L")
      (description "贴片电阻")
      (fields (field (name "版权归属") "源创客"))
      (libsource (lib "3.1   - 电阻-电容-电感") (part "R"))
    )
    (comp (ref "R98")
      (value "4.7R")
      (footprint "R 0603_L")
      (description "贴片电阻")
      (fields (field (name "版权归属") "源创客"))
      (libsource (lib "3.1   - 电阻-电容-电感") (part "R"))
    )
    (comp (ref "R99")
      (value "4.7R")
      (footprint "R 0603_L")
      (description "贴片电阻")
      (fields (field (name "版权归属") "源创客"))
      (libsource (lib "3.1   - 电阻-电容-电感") (part "R"))
    )
    (comp (ref "R100")
      (value "4.7R")
      (footprint "R 0603_L")
      (description "贴片电阻")
      (fields (field (name "版权归属") "源创客"))
      (libsource (lib "3.1   - 电阻-电容-电感") (part "R"))
    )
    (comp (ref "R101")
      (value "10K")
      (footprint "R 0603_L")
      (description "贴片电阻")
      (fields (field (name "版权归属") "源创客"))
      (libsource (lib "3.1   - 电阻-电容-电感") (part "R"))
    )
    (comp (ref "R102")
      (value "10K")
      (footprint "R 0603_L")
      (description "贴片电阻")
      (fields (field (name "版权归属") "源创客"))
      (libsource (lib "3.1   - 电阻-电容-电感") (part "R"))
    )
    (comp (ref "R103")
      (value "10K")
      (footprint "R 0603_L")
      (description "贴片电阻")
      (fields (field (name "版权归属") "源创客"))
      (libsource (lib "3.1   - 电阻-电容-电感") (part "R"))
    )
    (comp (ref "R104")
      (value "4.7R")
      (footprint "R 0603_L")
      (description "贴片电阻")
      (fields (field (name "版权归属") "源创客"))
      (libsource (lib "3.1   - 电阻-电容-电感") (part "R"))
    )
    (comp (ref "R105")
      (value "4.7R")
      (footprint "R 0603_L")
      (description "贴片电阻")
      (fields (field (name "版权归属") "源创客"))
      (libsource (lib "3.1   - 电阻-电容-电感") (part "R"))
    )
    (comp (ref "R106")
      (value "4.7R")
      (footprint "R 0603_L")
      (description "贴片电阻")
      (fields (field (name "版权归属") "源创客"))
      (libsource (lib "3.1   - 电阻-电容-电感") (part "R"))
    )
    (comp (ref "R107")
      (value "10K")
      (footprint "R 0603_L")
      (description "贴片电阻")
      (fields (field (name "版权归属") "源创客"))
      (libsource (lib "3.1   - 电阻-电容-电感") (part "R"))
    )
    (comp (ref "R108")
      (value "10K")
      (footprint "R 0603_L")
      (description "贴片电阻")
      (fields (field (name "版权归属") "源创客"))
      (libsource (lib "3.1   - 电阻-电容-电感") (part "R"))
    )
    (comp (ref "R109")
      (value "10K")
      (footprint "R 0603_L")
      (description "贴片电阻")
      (fields (field (name "版权归属") "源创客"))
      (libsource (lib "3.1   - 电阻-电容-电感") (part "R"))
    )
    (comp (ref "R110")
      (value "4.7R")
      (footprint "R 0603_L")
      (description "贴片电阻")
      (fields (field (name "版权归属") "源创客"))
      (libsource (lib "3.1   - 电阻-电容-电感") (part "R"))
    )
    (comp (ref "R111")
      (value "4.7R")
      (footprint "R 0603_L")
      (description "贴片电阻")
      (fields (field (name "版权归属") "源创客"))
      (libsource (lib "3.1   - 电阻-电容-电感") (part "R"))
    )
    (comp (ref "R112")
      (value "4.7R")
      (footprint "R 0603_L")
      (description "贴片电阻")
      (fields (field (name "版权归属") "源创客"))
      (libsource (lib "3.1   - 电阻-电容-电感") (part "R"))
    )
    (comp (ref "R113")
      (value "50mR")
      (footprint "R 1206_M")
      (description "贴片电阻")
      (fields (field (name "版权归属") "源创客"))
      (libsource (lib "3.1   - 电阻-电容-电感") (part "R"))
    )
    (comp (ref "R114")
      (value "10K")
      (footprint "R 0603_L")
      (description "贴片电阻")
      (fields (field (name "版权归属") "源创客"))
      (libsource (lib "3.1   - 电阻-电容-电感") (part "R"))
    )
    (comp (ref "R115")
      (value "10K")
      (footprint "R 0603_L")
      (description "贴片电阻")
      (fields (field (name "版权归属") "源创客"))
      (libsource (lib "3.1   - 电阻-电容-电感") (part "R"))
    )
    (comp (ref "R116")
      (value "10K")
      (footprint "R 0603_L")
      (description "贴片电阻")
      (fields (field (name "版权归属") "源创客"))
      (libsource (lib "3.1   - 电阻-电容-电感") (part "R"))
    )
    (comp (ref "R117")
      (value "50mR")
      (footprint "R 1206_M")
      (description "贴片电阻")
      (fields (field (name "版权归属") "源创客"))
      (libsource (lib "3.1   - 电阻-电容-电感") (part "R"))
    )
    (comp (ref "S1")
      (value "SW-SPDT")
      (footprint "SS12D10")
      (description "单刀双掷开关 3脚船型、钮子、拨动开关 SPDT Subminiature Toggle Switch")
      (fields (field (name "PUBLISHER") "Altium Limited"))
      (libsource (lib "无刷驱动_CH32V307_V1.0") (part "SW-SPDT"))
    )
    (comp (ref "S2")
      (value "SW-SPDT")
      (footprint "SS12D10")
      (description "单刀双掷开关 3脚船型、钮子、拨动开关 SPDT Subminiature Toggle Switch")
      (fields (field (name "PUBLISHER") "Altium Limited"))
      (libsource (lib "无刷驱动_CH32V307_V1.0") (part "SW-SPDT"))
    )
    (comp (ref "U1")
      (value "CH32V307VCT6")
      (footprint "LQFP100_N")
      (description "CH32V307VCT6 沁恒32位RISCV单片机")
      (fields (field (name "PUBLISHER") "Altium Limited"))
      (libsource (lib "无刷驱动_CH32V307_V1.0") (part "CH32V307VCT6"))
    )
    (comp (ref "U2")
      (value "RY8121")
      (footprint "SOT-23-6")
      (description "18V 2A 1MHz Synchronous Step-Down Regulator")
      (libsource (lib "无刷驱动_CH32V307_V1.0") (part "RY8121"))
    )
    (comp (ref "U3")
      (value "RT9013-33")
      (footprint "SOT-23-5")
      (description "3.3V 500mA SOT-23-5 LDO")
      (libsource (lib "无刷驱动_CH32V307_V1.0") (part "RT9013-33"))
    )
    (comp (ref "U4")
      (value "ETA7014")
      (footprint "SOT-23-6")
      (description "ETA7014 OVP芯片")
      (libsource (lib "无刷驱动_CH32V307_V1.0") (part "ETA7014"))
    )
    (comp (ref "U5")
      (value "FD6288Q")
      (footprint "QFN24-4x4")
      (description "FD6288Q 三相栅极驱动器")
      (libsource (lib "无刷驱动_CH32V307_V1.0") (part "FD6288Q"))
    )
    (comp (ref "U6")
      (value "FD6288Q")
      (footprint "QFN24-4x4")
      (description "FD6288Q 三相栅极驱动器")
      (libsource (lib "无刷驱动_CH32V307_V1.0") (part "FD6288Q"))
    )
    (comp (ref "Y1")
      (value "8MHz")
      (footprint "X3225-4")
      (description "四脚无源晶振 Crystal Oscillator")
      (fields
        (field (name "LOAD CAPACTIANCE") "20pF")
        (field (name "FREQUENCY") "8MHz")
        (field (name "PUBLISHER") "Altium Limited")
      )
      (libsource (lib "无刷驱动_CH32V307_V1.0") (part "XTAL-4"))
    )
  )
  (nets
    (net (code "1") (name "/BATADC") (class "Default")
      (node (ref "R61") (pin "2") (pinfunction "2_2") (pintype "passive"))
      (node (ref "U1") (pin "15") (pinfunction "ADC10/PC0_15") (pintype "passive"))
    )
    (net (code "2") (name "/BREAK1") (class "Default")
      (node (ref "D1") (pin "K") (pinfunction "K_K") (pintype "passive"))
      (node (ref "D2") (pin "K") (pinfunction "K_K") (pintype "passive"))
      (node (ref "R8") (pin "1") (pinfunction "1_1") (pintype "passive"))
      (node (ref "U1") (pin "31") (pinfunction "PA6/ADC6_31") (pintype "passive"))
    )
    (net (code "3") (name "/BREAK2") (class "Default")
      (node (ref "D3") (pin "K") (pinfunction "K_K") (pintype "passive"))
      (node (ref "D4") (pin "K") (pinfunction "K_K") (pintype "passive"))
      (node (ref "R32") (pin "1") (pinfunction "1_1") (pintype "passive"))
      (node (ref "U1") (pin "61") (pinfunction "PD14_61") (pintype "passive"))
    )
    (net (code "4") (name "/CLK") (class "Default")
      (node (ref "JP1") (pin "4") (pinfunction "4_4") (pintype "passive"))
      (node (ref "U1") (pin "76") (pinfunction "PA14/SWCLK_76") (pintype "passive"))
    )
    (net (code "5") (name "/CU_SUM1") (class "Default")
      (node (ref "C1") (pin "2") (pinfunction "2_2") (pintype "passive"))
      (node (ref "R4") (pin "1") (pinfunction "1_1") (pintype "passive"))
      (node (ref "R6") (pin "2") (pinfunction "2_2") (pintype "passive"))
      (node (ref "U1") (pin "16") (pinfunction "ADC11/PC1_16") (pintype "passive"))
    )
    (net (code "6") (name "/CU_SUM2") (class "Default")
      (node (ref "C2") (pin "2") (pinfunction "2_2") (pintype "passive"))
      (node (ref "R21") (pin "1") (pinfunction "1_1") (pintype "passive"))
      (node (ref "R24") (pin "2") (pinfunction "2_2") (pintype "passive"))
      (node (ref "U1") (pin "29") (pinfunction "PA4/ADC4/DAC0_29") (pintype "passive"))
    )
    (net (code "7") (name "/DBG_RX") (class "Default")
      (node (ref "JP1") (pin "9") (pinfunction "9_9") (pintype "passive"))
      (node (ref "U1") (pin "98") (pinfunction "PE1_98") (pintype "passive"))
    )
    (net (code "8") (name "/DBG_TX") (class "Default")
      (node (ref "JP1") (pin "7") (pinfunction "7_7") (pintype "passive"))
      (node (ref "U1") (pin "97") (pinfunction "PE0_97") (pintype "passive"))
    )
    (net (code "9") (name "/DIO") (class "Default")
      (node (ref "JP1") (pin "2") (pinfunction "2_2") (pintype "passive"))
      (node (ref "U1") (pin "72") (pinfunction "PA13/SWDIO_72") (pintype "passive"))
    )
    (net (code "10") (name "/DIRIN1") (class "Default")
      (node (ref "R29") (pin "1") (pinfunction "1_1") (pintype "passive"))
      (node (ref "R33") (pin "1") (pinfunction "1_1") (pintype "passive"))
      (node (ref "U1") (pin "2") (pinfunction "PE3_2") (pintype "passive"))
    )
    (net (code "11") (name "/DIRIN2") (class "Default")
      (node (ref "R52") (pin "1") (pinfunction "1_1") (pintype "passive"))
      (node (ref "R55") (pin "1") (pinfunction "1_1") (pintype "passive"))
      (node (ref "U1") (pin "4") (pinfunction "PE5_4") (pintype "passive"))
    )
    (net (code "12") (name "/DIROUT1") (class "Default")
      (node (ref "R9") (pin "1") (pinfunction "1_1") (pintype "passive"))
      (node (ref "U1") (pin "1") (pinfunction "PE2_1") (pintype "passive"))
    )
    (net (code "13") (name "/DIROUT2") (class "Default")
      (node (ref "R36") (pin "1") (pinfunction "1_1") (pintype "passive"))
      (node (ref "U1") (pin "3") (pinfunction "PE4_3") (pintype "passive"))
    )
    (net (code "14") (name "/EN1") (class "Default")
      (node (ref "LED1") (pin "C") (pinfunction "C_C") (pintype "passive"))
      (node (ref "U1") (pin "41") (pinfunction "PE10_41") (pintype "passive"))
    )
    (net (code "15") (name "/EN2") (class "Default")
      (node (ref "LED4") (pin "C") (pinfunction "C_C") (pintype "passive"))
      (node (ref "U1") (pin "85") (pinfunction "PD4_85") (pintype "passive"))
    )
    (net (code "16") (name "/ENKEY1") (class "Default")
      (node (ref "R19") (pin "1") (pinfunction "1_1") (pintype "passive"))
      (node (ref "U1") (pin "40") (pinfunction "PE9_40") (pintype "passive"))
    )
    (net (code "17") (name "/ENKEY2") (class "Default")
      (node (ref "R44") (pin "1") (pinfunction "1_1") (pintype "passive"))
      (node (ref "U1") (pin "79") (pinfunction "PC11_79") (pintype "passive"))
    )
    (net (code "18") (name "/ERR1") (class "Default")
      (node (ref "LED3") (pin "C") (pinfunction "C_C") (pintype "passive"))
      (node (ref "U1") (pin "43") (pinfunction "PE12_43") (pintype "passive"))
    )
    (net (code "19") (name "/ERR2") (class "Default")
      (node (ref "LED6") (pin "C") (pinfunction "C_C") (pintype "passive"))
      (node (ref "U1") (pin "87") (pinfunction "PD6_87") (pintype "passive"))
    )
    (net (code "20") (name "/HALLA1") (class "Default")
      (node (ref "C5") (pin "1") (pinfunction "1_1") (pintype "passive"))
      (node (ref "R15") (pin "1") (pinfunction "1_1") (pintype "passive"))
      (node (ref "R25") (pin "1") (pinfunction "1_1") (pintype "passive"))
      (node (ref "U1") (pin "63") (pinfunction "RXP/PC6_63") (pintype "passive"))
    )
    (net (code "21") (name "/HALLA2") (class "Default")
      (node (ref "C12") (pin "1") (pinfunction "1_1") (pintype "passive"))
      (node (ref "R40") (pin "1") (pinfunction "1_1") (pintype "passive"))
      (node (ref "R47") (pin "1") (pinfunction "1_1") (pintype "passive"))
      (node (ref "U1") (pin "92") (pinfunction "PB6/USB2DM_92") (pintype "passive"))
    )
    (net (code "22") (name "/HALLB1") (class "Default")
      (node (ref "C4") (pin "1") (pinfunction "1_1") (pintype "passive"))
      (node (ref "R14") (pin "1") (pinfunction "1_1") (pintype "passive"))
      (node (ref "R26") (pin "1") (pinfunction "1_1") (pintype "passive"))
      (node (ref "U1") (pin "64") (pinfunction "RXN/PC7_64") (pintype "passive"))
    )
    (net (code "23") (name "/HALLB2") (class "Default")
      (node (ref "C11") (pin "1") (pinfunction "1_1") (pintype "passive"))
      (node (ref "R39") (pin "1") (pinfunction "1_1") (pintype "passive"))
      (node (ref "R48") (pin "1") (pinfunction "1_1") (pintype "passive"))
      (node (ref "U1") (pin "93") (pinfunction "PB7/USB2DP_93") (pintype "passive"))
    )
    (net (code "24") (name "/HALLC1") (class "Default")
      (node (ref "C3") (pin "1") (pinfunction "1_1") (pintype "passive"))
      (node (ref "R13") (pin "1") (pinfunction "1_1") (pintype "passive"))
      (node (ref "R28") (pin "1") (pinfunction "1_1") (pintype "passive"))
      (node (ref "U1") (pin "65") (pinfunction "TXP/PC8_65") (pintype "passive"))
    )
    (net (code "25") (name "/HALLC2") (class "Default")
      (node (ref "C10") (pin "1") (pinfunction "1_1") (pintype "passive"))
      (node (ref "R38") (pin "1") (pinfunction "1_1") (pintype "passive"))
      (node (ref "R50") (pin "1") (pinfunction "1_1") (pintype "passive"))
      (node (ref "U1") (pin "95") (pinfunction "PB8_95") (pintype "passive"))
    )
    (net (code "26") (name "/HOA1") (class "Default")
      (node (ref "R92") (pin "1") (pinfunction "1_1") (pintype "passive"))
      (node (ref "U5") (pin "19") (pinfunction "HO1_19") (pintype "passive"))
    )
    (net (code "27") (name "/HOA2") (class "Default")
      (node (ref "R98") (pin "1") (pinfunction "1_1") (pintype "passive"))
      (node (ref "U6") (pin "19") (pinfunction "HO1_19") (pintype "passive"))
    )
    (net (code "28") (name "/HOB1") (class "Default")
      (node (ref "R93") (pin "1") (pinfunction "1_1") (pintype "passive"))
      (node (ref "U5") (pin "16") (pinfunction "HO2_16") (pintype "passive"))
    )
    (net (code "29") (name "/HOB2") (class "Default")
      (node (ref "R99") (pin "1") (pinfunction "1_1") (pintype "passive"))
      (node (ref "U6") (pin "16") (pinfunction "HO2_16") (pintype "passive"))
    )
    (net (code "30") (name "/HOC1") (class "Default")
      (node (ref "R94") (pin "1") (pinfunction "1_1") (pintype "passive"))
      (node (ref "U5") (pin "13") (pinfunction "HO3_13") (pintype "passive"))
    )
    (net (code "31") (name "/HOC2") (class "Default")
      (node (ref "R100") (pin "1") (pinfunction "1_1") (pintype "passive"))
      (node (ref "U6") (pin "13") (pinfunction "HO3_13") (pintype "passive"))
    )
    (net (code "32") (name "/ISUM1") (class "Default")
      (node (ref "Q7") (pin "3") (pinfunction "S_3") (pintype "passive"))
      (node (ref "Q8") (pin "3") (pinfunction "S_3") (pintype "passive"))
      (node (ref "Q9") (pin "3") (pinfunction "S_3") (pintype "passive"))
      (node (ref "R107") (pin "2") (pinfunction "2_2") (pintype "passive"))
      (node (ref "R108") (pin "2") (pinfunction "2_2") (pintype "passive"))
      (node (ref "R109") (pin "2") (pinfunction "2_2") (pintype "passive"))
      (node (ref "R113") (pin "2") (pinfunction "2_2") (pintype "passive"))
      (node (ref "R7") (pin "1") (pinfunction "1_1") (pintype "passive"))
    )
    (net (code "33") (name "/ISUM2") (class "Default")
      (node (ref "Q10") (pin "3") (pinfunction "S_3") (pintype "passive"))
      (node (ref "Q11") (pin "3") (pinfunction "S_3") (pintype "passive"))
      (node (ref "Q12") (pin "3") (pinfunction "S_3") (pintype "passive"))
      (node (ref "R114") (pin "2") (pinfunction "2_2") (pintype "passive"))
      (node (ref "R115") (pin "2") (pinfunction "2_2") (pintype "passive"))
      (node (ref "R116") (pin "2") (pinfunction "2_2") (pintype "passive"))
      (node (ref "R117") (pin "2") (pinfunction "2_2") (pintype "passive"))
      (node (ref "R31") (pin "1") (pinfunction "1_1") (pintype "passive"))
    )
    (net (code "34") (name "/LOA1") (class "Default")
      (node (ref "R104") (pin "1") (pinfunction "1_1") (pintype "passive"))
      (node (ref "U5") (pin "11") (pinfunction "LO1_11") (pintype "passive"))
    )
    (net (code "35") (name "/LOA2") (class "Default")
      (node (ref "R110") (pin "1") (pinfunction "1_1") (pintype "passive"))
      (node (ref "U6") (pin "11") (pinfunction "LO1_11") (pintype "passive"))
    )
    (net (code "36") (name "/LOB1") (class "Default")
      (node (ref "R105") (pin "1") (pinfunction "1_1") (pintype "passive"))
      (node (ref "U5") (pin "10") (pinfunction "LO2_10") (pintype "passive"))
    )
    (net (code "37") (name "/LOB2") (class "Default")
      (node (ref "R111") (pin "1") (pinfunction "1_1") (pintype "passive"))
      (node (ref "U6") (pin "10") (pinfunction "LO2_10") (pintype "passive"))
    )
    (net (code "38") (name "/LOC1") (class "Default")
      (node (ref "R106") (pin "1") (pinfunction "1_1") (pintype "passive"))
      (node (ref "U5") (pin "9") (pinfunction "LO3_9") (pintype "passive"))
    )
    (net (code "39") (name "/LOC2") (class "Default")
      (node (ref "R112") (pin "1") (pinfunction "1_1") (pintype "passive"))
      (node (ref "U6") (pin "9") (pinfunction "LO3_9") (pintype "passive"))
    )
    (net (code "40") (name "/NTC1") (class "Default")
      (node (ref "R22") (pin "1") (pinfunction "1_1") (pintype "passive"))
      (node (ref "U1") (pin "30") (pinfunction "PA5/ADC5/DAC1_30") (pintype "passive"))
    )
    (net (code "41") (name "/NTC2") (class "Default")
      (node (ref "R46") (pin "1") (pinfunction "1_1") (pintype "passive"))
      (node (ref "U1") (pin "24") (pinfunction "PA1/ADC1_24") (pintype "passive"))
    )
    (net (code "42") (name "/OP1N") (class "Default")
      (node (ref "R1") (pin "1") (pinfunction "1_1") (pintype "passive"))
      (node (ref "R5") (pin "2") (pinfunction "2_2") (pintype "passive"))
      (node (ref "U1") (pin "48") (pinfunction "PB11_48") (pintype "passive"))
    )
    (net (code "43") (name "/OP1O") (class "Default")
      (node (ref "R1") (pin "2") (pinfunction "2_2") (pintype "passive"))
      (node (ref "R6") (pin "1") (pinfunction "1_1") (pintype "passive"))
      (node (ref "U1") (pin "26") (pinfunction "PA3/ADC3_26") (pintype "passive"))
    )
    (net (code "44") (name "/OP1P") (class "Default")
      (node (ref "R7") (pin "2") (pinfunction "2_2") (pintype "passive"))
      (node (ref "U1") (pin "54") (pinfunction "PB15_54") (pintype "passive"))
    )
    (net (code "45") (name "/OP2N") (class "Default")
      (node (ref "R2") (pin "2") (pinfunction "2_2") (pintype "passive"))
      (node (ref "R3") (pin "2") (pinfunction "2_2") (pintype "passive"))
      (node (ref "U1") (pin "47") (pinfunction "PB10_47") (pintype "passive"))
    )
    (net (code "46") (name "/OP2O") (class "Default")
      (node (ref "D1") (pin "A") (pinfunction "A_A") (pintype "passive"))
      (node (ref "U1") (pin "25") (pinfunction "PA2/ADC2_25") (pintype "passive"))
    )
    (net (code "47") (name "/OP2P") (class "Default")
      (node (ref "R4") (pin "2") (pinfunction "2_2") (pintype "passive"))
      (node (ref "U1") (pin "53") (pinfunction "PB14_53") (pintype "passive"))
    )
    (net (code "48") (name "/OP3N") (class "Default")
      (node (ref "R11") (pin "1") (pinfunction "1_1") (pintype "passive"))
      (node (ref "R23") (pin "2") (pinfunction "2_2") (pintype "passive"))
      (node (ref "U1") (pin "17") (pinfunction "ADC12/PC2_17") (pintype "passive"))
    )
    (net (code "49") (name "/OP3O") (class "Default")
      (node (ref "R11") (pin "2") (pinfunction "2_2") (pintype "passive"))
      (node (ref "R24") (pin "1") (pinfunction "1_1") (pintype "passive"))
      (node (ref "U1") (pin "38") (pinfunction "PE7_38") (pintype "passive"))
    )
    (net (code "50") (name "/OP3P") (class "Default")
      (node (ref "R31") (pin "2") (pinfunction "2_2") (pintype "passive"))
      (node (ref "U1") (pin "34") (pinfunction "ADC15/PC5_34") (pintype "passive"))
    )
    (net (code "51") (name "/OP4N") (class "Default")
      (node (ref "R12") (pin "2") (pinfunction "2_2") (pintype "passive"))
      (node (ref "R18") (pin "2") (pinfunction "2_2") (pintype "passive"))
      (node (ref "U1") (pin "18") (pinfunction "ADC13/PC3_18") (pintype "passive"))
    )
    (net (code "52") (name "/OP4O") (class "Default")
      (node (ref "D3") (pin "A") (pinfunction "A_A") (pintype "passive"))
      (node (ref "U1") (pin "39") (pinfunction "PE8_39") (pintype "passive"))
    )
    (net (code "53") (name "/OP4P") (class "Default")
      (node (ref "R21") (pin "2") (pinfunction "2_2") (pintype "passive"))
      (node (ref "U1") (pin "33") (pinfunction "ADC14/PC4_33") (pintype "passive"))
    )
    (net (code "54") (name "/PWMAH1") (class "Default")
      (node (ref "R68") (pin "1") (pinfunction "1_1") (pintype "passive"))
      (node (ref "U1") (pin "67") (pinfunction "PA8_67") (pintype "passive"))
    )
    (net (code "55") (name "/PWMAH2") (class "Default")
      (node (ref "R69") (pin "1") (pinfunction "1_1") (pintype "passive"))
      (node (ref "U1") (pin "56") (pinfunction "PD9_56") (pintype "passive"))
    )
    (net (code "56") (name "/PWMAL1") (class "Default")
      (node (ref "R72") (pin "1") (pinfunction "1_1") (pintype "passive"))
      (node (ref "U1") (pin "32") (pinfunction "PA7/ADC7_32") (pintype "passive"))
    )
    (net (code "57") (name "/PWMAL2") (class "Default")
      (node (ref "R73") (pin "1") (pinfunction "1_1") (pintype "passive"))
      (node (ref "U1") (pin "55") (pinfunction "PD8_55") (pintype "passive"))
    )
    (net (code "58") (name "/PWMBH1") (class "Default")
      (node (ref "R76") (pin "1") (pinfunction "1_1") (pintype "passive"))
      (node (ref "U1") (pin "68") (pinfunction "PA9_68") (pintype "passive"))
    )
    (net (code "59") (name "/PWMBH2") (class "Default")
      (node (ref "R77") (pin "1") (pinfunction "1_1") (pintype "passive"))
      (node (ref "U1") (pin "58") (pinfunction "PD11_58") (pintype "passive"))
    )
    (net (code "60") (name "/PWMBL1") (class "Default")
      (node (ref "R80") (pin "1") (pinfunction "1_1") (pintype "passive"))
      (node (ref "U1") (pin "35") (pinfunction "PB0/ADC8_35") (pintype "passive"))
    )
    (net (code "61") (name "/PWMBL2") (class "Default")
      (node (ref "R81") (pin "1") (pinfunction "1_1") (pintype "passive"))
      (node (ref "U1") (pin "57") (pinfunction "PD10_57") (pintype "passive"))
    )
    (net (code "62") (name "/PWMCH1") (class "Default")
      (node (ref "R84") (pin "1") (pinfunction "1_1") (pintype "passive"))
      (node (ref "U1") (pin "69") (pinfunction "PA10_69") (pintype "passive"))
    )
    (net (code "63") (name "/PWMCH2") (class "Default")
      (node (ref "R85") (pin "1") (pinfunction "1_1") (pintype "passive"))
      (node (ref "U1") (pin "60") (pinfunction "PD13_60") (pintype "passive"))
    )
    (net (code "64") (name "/PWMCL1") (class "Default")
      (node (ref "R88") (pin "1") (pinfunction "1_1") (pintype "passive"))
      (node (ref "U1") (pin "36") (pinfunction "PB1/ADC9_36") (pintype "passive"))
    )
    (net (code "65") (name "/PWMCL2") (class "Default")
      (node (ref "R89") (pin "1") (pinfunction "1_1") (pintype "passive"))
      (node (ref "U1") (pin "59") (pinfunction "PD12_59") (pintype "passive"))
    )
    (net (code "66") (name "/PWMIN1") (class "Default")
      (node (ref "R30") (pin "2") (pinfunction "2_2") (pintype "passive"))
      (node (ref "R34") (pin "2") (pinfunction "2_2") (pintype "passive"))
      (node (ref "U1") (pin "89") (pinfunction "PB3_89") (pintype "passive"))
    )
    (net (code "67") (name "/PWMIN2") (class "Default")
      (node (ref "R53") (pin "2") (pinfunction "2_2") (pintype "passive"))
      (node (ref "R56") (pin "2") (pinfunction "2_2") (pintype "passive"))
      (node (ref "U1") (pin "84") (pinfunction "PD3_84") (pintype "passive"))
    )
    (net (code "68") (name "/RST") (class "Default")
      (node (ref "C9") (pin "2") (pinfunction "2_2") (pintype "passive"))
      (node (ref "JP1") (pin "10") (pinfunction "10_10") (pintype "passive"))
      (node (ref "R51") (pin "2") (pinfunction "2_2") (pintype "passive"))
      (node (ref "U1") (pin "14") (pinfunction "NRST_14") (pintype "passive"))
    )
    (net (code "69") (name "/RUN1") (class "Default")
      (node (ref "LED2") (pin "C") (pinfunction "C_C") (pintype "passive"))
      (node (ref "U1") (pin "42") (pinfunction "PE11_42") (pintype "passive"))
    )
    (net (code "70") (name "/RUN2") (class "Default")
      (node (ref "LED5") (pin "C") (pinfunction "C_C") (pintype "passive"))
      (node (ref "U1") (pin "86") (pinfunction "PD5_86") (pintype "passive"))
    )
    (net (code "71") (name "/SPDOUT1") (class "Default")
      (node (ref "R10") (pin "2") (pinfunction "2_2") (pintype "passive"))
      (node (ref "U1") (pin "23") (pinfunction "PA0/ADC0/WKUP_23") (pintype "passive"))
    )
    (net (code "72") (name "/SPDOUT2") (class "Default")
      (node (ref "R37") (pin "2") (pinfunction "2_2") (pintype "passive"))
      (node (ref "U1") (pin "66") (pinfunction "TXN/PC9_66") (pintype "passive"))
    )
    (net (code "73") (name "/VDDA") (class "Default")
      (node (ref "C30") (pin "2") (pinfunction "2_2") (pintype "passive"))
      (node (ref "FB1") (pin "2") (pinfunction "2_2") (pintype "passive"))
      (node (ref "R57") (pin "1") (pinfunction "1_1") (pintype "passive"))
      (node (ref "U1") (pin "22") (pinfunction "VDDA_22") (pintype "passive"))
    )
    (net (code "74") (name "/VSA1") (class "Default")
      (node (ref "C32") (pin "1") (pinfunction "1_1") (pintype "passive"))
      (node (ref "JP7") (pin "1") (pinfunction "1_1") (pintype "passive"))
      (node (ref "Q1") (pin "3") (pinfunction "S_3") (pintype "passive"))
      (node (ref "Q7") (pin "1") (pinfunction "D_1") (pintype "passive"))
      (node (ref "R95") (pin "2") (pinfunction "2_2") (pintype "passive"))
      (node (ref "U5") (pin "18") (pinfunction "VS1_18") (pintype "passive"))
    )
    (net (code "75") (name "/VSA2") (class "Default")
      (node (ref "C33") (pin "1") (pinfunction "1_1") (pintype "passive"))
      (node (ref "JP8") (pin "1") (pinfunction "1_1") (pintype "passive"))
      (node (ref "Q10") (pin "1") (pinfunction "D_1") (pintype "passive"))
      (node (ref "Q4") (pin "3") (pinfunction "S_3") (pintype "passive"))
      (node (ref "R101") (pin "2") (pinfunction "2_2") (pintype "passive"))
      (node (ref "U6") (pin "18") (pinfunction "VS1_18") (pintype "passive"))
    )
    (net (code "76") (name "/VSB1") (class "Default")
      (node (ref "C34") (pin "1") (pinfunction "1_1") (pintype "passive"))
      (node (ref "JP7") (pin "2") (pinfunction "2_2") (pintype "passive"))
      (node (ref "Q2") (pin "3") (pinfunction "S_3") (pintype "passive"))
      (node (ref "Q8") (pin "1") (pinfunction "D_1") (pintype "passive"))
      (node (ref "R96") (pin "2") (pinfunction "2_2") (pintype "passive"))
      (node (ref "U5") (pin "15") (pinfunction "VS2_15") (pintype "passive"))
    )
    (net (code "77") (name "/VSB2") (class "Default")
      (node (ref "C35") (pin "1") (pinfunction "1_1") (pintype "passive"))
      (node (ref "JP8") (pin "2") (pinfunction "2_2") (pintype "passive"))
      (node (ref "Q11") (pin "1") (pinfunction "D_1") (pintype "passive"))
      (node (ref "Q5") (pin "3") (pinfunction "S_3") (pintype "passive"))
      (node (ref "R102") (pin "2") (pinfunction "2_2") (pintype "passive"))
      (node (ref "U6") (pin "15") (pinfunction "VS2_15") (pintype "passive"))
    )
    (net (code "78") (name "/VSC1") (class "Default")
      (node (ref "C36") (pin "1") (pinfunction "1_1") (pintype "passive"))
      (node (ref "JP7") (pin "3") (pinfunction "3_3") (pintype "passive"))
      (node (ref "Q3") (pin "3") (pinfunction "S_3") (pintype "passive"))
      (node (ref "Q9") (pin "1") (pinfunction "D_1") (pintype "passive"))
      (node (ref "R97") (pin "2") (pinfunction "2_2") (pintype "passive"))
      (node (ref "U5") (pin "12") (pinfunction "VS3_12") (pintype "passive"))
    )
    (net (code "79") (name "/VSC2") (class "Default")
      (node (ref "C37") (pin "1") (pinfunction "1_1") (pintype "passive"))
      (node (ref "JP8") (pin "3") (pinfunction "3_3") (pintype "passive"))
      (node (ref "Q12") (pin "1") (pinfunction "D_1") (pintype "passive"))
      (node (ref "Q6") (pin "3") (pinfunction "S_3") (pintype "passive"))
      (node (ref "R103") (pin "2") (pinfunction "2_2") (pintype "passive"))
      (node (ref "U6") (pin "12") (pinfunction "VS3_12") (pintype "passive"))
    )
    (net (code "80") (name "/VSSA") (class "Default")
      (node (ref "C30") (pin "1") (pinfunction "1_1") (pintype "passive"))
      (node (ref "FB2") (pin "1") (pinfunction "1_1") (pintype "passive"))
      (node (ref "R54") (pin "1") (pinfunction "1_1") (pintype "passive"))
      (node (ref "U1") (pin "19") (pinfunction "VSSA_19") (pintype "passive"))
    )
    (net (code "81") (name "3V3") (class "Default")
      (node (ref "C14") (pin "2") (pinfunction "2_2") (pintype "passive"))
      (node (ref "C19") (pin "2") (pinfunction "2_2") (pintype "passive"))
      (node (ref "C20") (pin "2") (pinfunction "2_2") (pintype "passive"))
      (node (ref "C21") (pin "2") (pinfunction "2_2") (pintype "passive"))
      (node (ref "C24") (pin "2") (pinfunction "2_2") (pintype "passive"))
      (node (ref "C25") (pin "2") (pinfunction "2_2") (pintype "passive"))
      (node (ref "C26") (pin "2") (pinfunction "2_2") (pintype "passive"))
      (node (ref "D8") (pin "K") (pinfunction "K_K") (pintype "passive"))
      (node (ref "D9") (pin "K") (pinfunction "K_K") (pintype "passive"))
      (node (ref "FB1") (pin "1") (pinfunction "1_1") (pintype "passive"))
      (node (ref "JP1") (pin "1") (pinfunction "1_1") (pintype "passive"))
      (node (ref "R12") (pin "1") (pinfunction "1_1") (pintype "passive"))
      (node (ref "R13") (pin "2") (pinfunction "2_2") (pintype "passive"))
      (node (ref "R14") (pin "2") (pinfunction "2_2") (pintype "passive"))
      (node (ref "R15") (pin "2") (pinfunction "2_2") (pintype "passive"))
      (node (ref "R16") (pin "2") (pinfunction "2_2") (pintype "passive"))
      (node (ref "R17") (pin "1") (pinfunction "1_1") (pintype "passive"))
      (node (ref "R2") (pin "1") (pinfunction "1_1") (pintype "passive"))
      (node (ref "R20") (pin "1") (pinfunction "1_1") (pintype "passive"))
      (node (ref "R27") (pin "1") (pinfunction "1_1") (pintype "passive"))
      (node (ref "R38") (pin "2") (pinfunction "2_2") (pintype "passive"))
      (node (ref "R39") (pin "2") (pinfunction "2_2") (pintype "passive"))
      (node (ref "R40") (pin "2") (pinfunction "2_2") (pintype "passive"))
      (node (ref "R41") (pin "2") (pinfunction "2_2") (pintype "passive"))
      (node (ref "R42") (pin "1") (pinfunction "1_1") (pintype "passive"))
      (node (ref "R45") (pin "1") (pinfunction "1_1") (pintype "passive"))
      (node (ref "R49") (pin "1") (pinfunction "1_1") (pintype "passive"))
      (node (ref "R51") (pin "1") (pinfunction "1_1") (pintype "passive"))
      (node (ref "R58") (pin "1") (pinfunction "1_1") (pintype "passive"))
      (node (ref "R62") (pin "1") (pinfunction "1_1") (pintype "passive"))
      (node (ref "S1") (pin "3") (pintype "passive"))
      (node (ref "S2") (pin "3") (pintype "passive"))
      (node (ref "U1") (pin "100") (pinfunction "VIO_3_100") (pintype "passive"))
      (node (ref "U1") (pin "11") (pinfunction "VDD_5_11") (pintype "passive"))
      (node (ref "U1") (pin "28") (pinfunction "VDD_4_28") (pintype "passive"))
      (node (ref "U1") (pin "50") (pinfunction "VDD_1_50") (pintype "passive"))
      (node (ref "U1") (pin "75") (pinfunction "VDD_2_75") (pintype "passive"))
      (node (ref "U3") (pin "5") (pinfunction "OUT_5") (pintype "passive"))
    )
    (net (code "82") (name "5V") (class "Default")
      (node (ref "C15") (pin "2") (pinfunction "2_2") (pintype "passive"))
      (node (ref "C16") (pin "2") (pinfunction "2_2") (pintype "passive"))
      (node (ref "C17") (pin "2") (pinfunction "2_2") (pintype "passive"))
      (node (ref "C22") (pin "2") (pinfunction "2_2") (pintype "passive"))
      (node (ref "C23") (pin "2") (pinfunction "2_2") (pintype "passive"))
      (node (ref "JP3") (pin "1") (pinfunction "1_1") (pintype "passive"))
      (node (ref "JP5") (pin "1") (pinfunction "1_1") (pintype "passive"))
      (node (ref "L1") (pin "1") (pinfunction "1_1") (pintype "passive"))
      (node (ref "R59") (pin "2") (pinfunction "2_2") (pintype "passive"))
      (node (ref "U3") (pin "1") (pinfunction "IN_1") (pintype "passive"))
      (node (ref "U3") (pin "3") (pinfunction "EN_3") (pintype "passive"))
    )
    (net (code "83") (name "12V") (class "Default")
      (node (ref "C31") (pin "2") (pinfunction "2_2") (pintype "passive"))
      (node (ref "C38") (pin "2") (pinfunction "2_2") (pintype "passive"))
      (node (ref "C39") (pin "2") (pinfunction "2_2") (pintype "passive"))
      (node (ref "D10") (pin "A") (pinfunction "A_A") (pintype "passive"))
      (node (ref "D11") (pin "A") (pinfunction "A_A") (pintype "passive"))
      (node (ref "D12") (pin "A") (pinfunction "A_A") (pintype "passive"))
      (node (ref "D13") (pin "A") (pinfunction "A_A") (pintype "passive"))
      (node (ref "D14") (pin "A") (pinfunction "A_A") (pintype "passive"))
      (node (ref "D15") (pin "A") (pinfunction "A_A") (pintype "passive"))
      (node (ref "U2") (pin "4") (pinfunction "EN_4") (pintype "passive"))
      (node (ref "U2") (pin "5") (pinfunction "IN_5") (pintype "passive"))
      (node (ref "U4") (pin "3") (pinfunction "OUT_3") (pintype "passive"))
      (node (ref "U5") (pin "4") (pinfunction "VCC_4") (pintype "passive"))
      (node (ref "U6") (pin "4") (pinfunction "VCC_4") (pintype "passive"))
    )
    (net (code "84") (name "GND") (class "Default")
      (node (ref "C1") (pin "1") (pinfunction "1_1") (pintype "passive"))
      (node (ref "C10") (pin "2") (pinfunction "2_2") (pintype "passive"))
      (node (ref "C11") (pin "2") (pinfunction "2_2") (pintype "passive"))
      (node (ref "C12") (pin "2") (pinfunction "2_2") (pintype "passive"))
      (node (ref "C13") (pin "1") (pinfunction "1_1") (pintype "passive"))
      (node (ref "C14") (pin "1") (pinfunction "1_1") (pintype "passive"))
      (node (ref "C15") (pin "1") (pinfunction "1_1") (pintype "passive"))
      (node (ref "C16") (pin "1") (pinfunction "1_1") (pintype "passive"))
      (node (ref "C19") (pin "1") (pinfunction "1_1") (pintype "passive"))
      (node (ref "C2") (pin "1") (pinfunction "1_1") (pintype "passive"))
      (node (ref "C20") (pin "1") (pinfunction "1_1") (pintype "passive"))
      (node (ref "C21") (pin "1") (pinfunction "1_1") (pintype "passive"))
      (node (ref "C26") (pin "1") (pinfunction "1_1") (pintype "passive"))
      (node (ref "C27") (pin "1") (pinfunction "1_1") (pintype "passive"))
      (node (ref "C28") (pin "1") (pinfunction "1_1") (pintype "passive"))
      (node (ref "C29") (pin "1") (pinfunction "1_1") (pintype "passive"))
      (node (ref "C3") (pin "2") (pinfunction "2_2") (pintype "passive"))
      (node (ref "C31") (pin "1") (pinfunction "1_1") (pintype "passive"))
      (node (ref "C38") (pin "1") (pinfunction "1_1") (pintype "passive"))
      (node (ref "C39") (pin "1") (pinfunction "1_1") (pintype "passive"))
      (node (ref "C4") (pin "2") (pinfunction "2_2") (pintype "passive"))
      (node (ref "C5") (pin "2") (pinfunction "2_2") (pintype "passive"))
      (node (ref "C6") (pin "1") (pinfunction "1_1") (pintype "passive"))
      (node (ref "C7") (pin "1") (pinfunction "1_1") (pintype "passive"))
      (node (ref "C8") (pin "1") (pinfunction "1_1") (pintype "passive"))
      (node (ref "C9") (pin "1") (pinfunction "1_1") (pintype "passive"))
      (node (ref "D6") (pin "2") (pinfunction "2_2") (pintype "passive"))
      (node (ref "D7") (pin "2") (pinfunction "2_2") (pintype "passive"))
      (node (ref "E1") (pin "2") (pinfunction "K_2") (pintype "passive"))
      (node (ref "E2") (pin "2") (pinfunction "K_2") (pintype "passive"))
      (node (ref "FB2") (pin "2") (pinfunction "2_2") (pintype "passive"))
      (node (ref "JP1") (pin "3") (pinfunction "3_3") (pintype "passive"))
      (node (ref "JP1") (pin "5") (pinfunction "5_5") (pintype "passive"))
      (node (ref "JP2") (pin "3") (pinfunction "3_3") (pintype "passive"))
      (node (ref "JP2") (pin "4") (pinfunction "4_4") (pintype "passive"))
      (node (ref "JP3") (pin "6") (pinfunction "6_6") (pintype "passive"))
      (node (ref "JP4") (pin "3") (pinfunction "3_3") (pintype "passive"))
      (node (ref "JP4") (pin "4") (pinfunction "4_4") (pintype "passive"))
      (node (ref "JP5") (pin "6") (pinfunction "6_6") (pintype "passive"))
      (node (ref "JP6") (pin "1") (pinfunction "1_1") (pintype "passive"))
      (node (ref "R113") (pin "1") (pinfunction "1_1") (pintype "passive"))
      (node (ref "R117") (pin "1") (pinfunction "1_1") (pintype "passive"))
      (node (ref "R18") (pin "1") (pinfunction "1_1") (pintype "passive"))
      (node (ref "R23") (pin "1") (pinfunction "1_1") (pintype "passive"))
      (node (ref "R3") (pin "1") (pinfunction "1_1") (pintype "passive"))
      (node (ref "R32") (pin "2") (pinfunction "2_2") (pintype "passive"))
      (node (ref "R33") (pin "2") (pinfunction "2_2") (pintype "passive"))
      (node (ref "R34") (pin "1") (pinfunction "1_1") (pintype "passive"))
      (node (ref "R43") (pin "1") (pinfunction "1_1") (pintype "passive"))
      (node (ref "R5") (pin "1") (pinfunction "1_1") (pintype "passive"))
      (node (ref "R55") (pin "2") (pinfunction "2_2") (pintype "passive"))
      (node (ref "R56") (pin "1") (pinfunction "1_1") (pintype "passive"))
      (node (ref "R63") (pin "1") (pinfunction "1_1") (pintype "passive"))
      (node (ref "R64") (pin "1") (pinfunction "1_1") (pintype "passive"))
      (node (ref "R67") (pin "2") (pinfunction "2_2") (pintype "passive"))
      (node (ref "R70") (pin "1") (pinfunction "1_1") (pintype "passive"))
      (node (ref "R71") (pin "1") (pinfunction "1_1") (pintype "passive"))
      (node (ref "R74") (pin "1") (pinfunction "1_1") (pintype "passive"))
      (node (ref "R75") (pin "1") (pinfunction "1_1") (pintype "passive"))
      (node (ref "R78") (pin "1") (pinfunction "1_1") (pintype "passive"))
      (node (ref "R79") (pin "1") (pinfunction "1_1") (pintype "passive"))
      (node (ref "R8") (pin "2") (pinfunction "2_2") (pintype "passive"))
      (node (ref "R82") (pin "1") (pinfunction "1_1") (pintype "passive"))
      (node (ref "R83") (pin "1") (pinfunction "1_1") (pintype "passive"))
      (node (ref "R86") (pin "1") (pinfunction "1_1") (pintype "passive"))
      (node (ref "R87") (pin "1") (pinfunction "1_1") (pintype "passive"))
      (node (ref "R90") (pin "1") (pinfunction "1_1") (pintype "passive"))
      (node (ref "R91") (pin "1") (pinfunction "1_1") (pintype "passive"))
      (node (ref "S1") (pin "1") (pintype "passive"))
      (node (ref "S2") (pin "1") (pintype "passive"))
      (node (ref "U1") (pin "10") (pinfunction "VSS_5_10") (pintype "passive"))
      (node (ref "U1") (pin "27") (pinfunction "VSS_4_27") (pintype "passive"))
      (node (ref "U1") (pin "49") (pinfunction "VSS_1_49") (pintype "passive"))
      (node (ref "U1") (pin "74") (pinfunction "VSS_2_74") (pintype "passive"))
      (node (ref "U1") (pin "99") (pinfunction "VSS_3_99") (pintype "passive"))
      (node (ref "U2") (pin "2") (pinfunction "GND_2") (pintype "passive"))
      (node (ref "U4") (pin "6") (pinfunction "GND_6") (pintype "passive"))
      (node (ref "U5") (pin "0") (pinfunction "EP_0") (pintype "passive"))
      (node (ref "U5") (pin "6") (pinfunction "COM_6") (pintype "passive"))
      (node (ref "U6") (pin "0") (pinfunction "EP_0") (pintype "passive"))
      (node (ref "U6") (pin "6") (pinfunction "COM_6") (pintype "passive"))
      (node (ref "Y1") (pin "2") (pinfunction "NC_2") (pintype "passive"))
      (node (ref "Y1") (pin "4") (pinfunction "NC_4") (pintype "passive"))
    )
    (net (code "85") (name "Net-(C6-Pad2)") (class "Default")
      (node (ref "C6") (pin "2") (pinfunction "2_2") (pintype "passive"))
      (node (ref "JP3") (pin "2") (pinfunction "2_2") (pintype "passive"))
      (node (ref "R16") (pin "1") (pinfunction "1_1") (pintype "passive"))
      (node (ref "R22") (pin "2") (pinfunction "2_2") (pintype "passive"))
    )
    (net (code "86") (name "Net-(C13-Pad2)") (class "Default")
      (node (ref "C13") (pin "2") (pinfunction "2_2") (pintype "passive"))
      (node (ref "JP5") (pin "2") (pinfunction "2_2") (pintype "passive"))
      (node (ref "R41") (pin "1") (pinfunction "1_1") (pintype "passive"))
      (node (ref "R46") (pin "2") (pinfunction "2_2") (pintype "passive"))
    )
    (net (code "87") (name "Net-(C27-Pad2)") (class "Default")
      (node (ref "C27") (pin "2") (pinfunction "2_2") (pintype "passive"))
      (node (ref "R60") (pin "1") (pinfunction "1_1") (pintype "passive"))
      (node (ref "R61") (pin "1") (pinfunction "1_1") (pintype "passive"))
      (node (ref "R64") (pin "2") (pinfunction "2_2") (pintype "passive"))
    )
    (net (code "88") (name "Net-(D2-PadA)") (class "Default")
      (node (ref "D2") (pin "A") (pinfunction "A_A") (pintype "passive"))
      (node (ref "R19") (pin "2") (pinfunction "2_2") (pintype "passive"))
      (node (ref "S1") (pin "2") (pintype "passive"))
    )
    (net (code "89") (name "Net-(D4-PadA)") (class "Default")
      (node (ref "D4") (pin "A") (pinfunction "A_A") (pintype "passive"))
      (node (ref "R44") (pin "2") (pinfunction "2_2") (pintype "passive"))
      (node (ref "S2") (pin "2") (pintype "passive"))
    )
    (net (code "90") (name "Net-(JP2-Pad1)") (class "Default")
      (node (ref "JP2") (pin "1") (pinfunction "1_1") (pintype "passive"))
      (node (ref "R29") (pin "2") (pinfunction "2_2") (pintype "passive"))
    )
    (net (code "91") (name "Net-(JP2-Pad2)") (class "Default")
      (node (ref "JP2") (pin "2") (pinfunction "2_2") (pintype "passive"))
      (node (ref "R9") (pin "2") (pinfunction "2_2") (pintype "passive"))
    )
    (net (code "92") (name "Net-(JP2-Pad5)") (class "Default")
      (node (ref "JP2") (pin "5") (pinfunction "5_5") (pintype "passive"))
      (node (ref "R30") (pin "1") (pinfunction "1_1") (pintype "passive"))
    )
    (net (code "93") (name "Net-(JP2-Pad6)") (class "Default")
      (node (ref "JP2") (pin "6") (pinfunction "6_6") (pintype "passive"))
      (node (ref "R10") (pin "1") (pinfunction "1_1") (pintype "passive"))
    )
    (net (code "94") (name "Net-(JP3-Pad3)") (class "Default")
      (node (ref "JP3") (pin "3") (pinfunction "3_3") (pintype "passive"))
      (node (ref "R25") (pin "2") (pinfunction "2_2") (pintype "passive"))
    )
    (net (code "95") (name "Net-(JP3-Pad4)") (class "Default")
      (node (ref "JP3") (pin "4") (pinfunction "4_4") (pintype "passive"))
      (node (ref "R26") (pin "2") (pinfunction "2_2") (pintype "passive"))
    )
    (net (code "96") (name "Net-(JP3-Pad5)") (class "Default")
      (node (ref "JP3") (pin "5") (pinfunction "5_5") (pintype "passive"))
      (node (ref "R28") (pin "2") (pinfunction "2_2") (pintype "passive"))
    )
    (net (code "97") (name "Net-(JP4-Pad1)") (class "Default")
      (node (ref "JP4") (pin "1") (pinfunction "1_1") (pintype "passive"))
      (node (ref "R52") (pin "2") (pinfunction "2_2") (pintype "passive"))
    )
    (net (code "98") (name "Net-(JP4-Pad2)") (class "Default")
      (node (ref "JP4") (pin "2") (pinfunction "2_2") (pintype "passive"))
      (node (ref "R36") (pin "2") (pinfunction "2_2") (pintype "passive"))
    )
    (net (code "99") (name "Net-(JP4-Pad5)") (class "Default")
      (node (ref "JP4") (pin "5") (pinfunction "5_5") (pintype "passive"))
      (node (ref "R53") (pin "1") (pinfunction "1_1") (pintype "passive"))
    )
    (net (code "100") (name "Net-(JP4-Pad6)") (class "Default")
      (node (ref "JP4") (pin "6") (pinfunction "6_6") (pintype "passive"))
      (node (ref "R37") (pin "1") (pinfunction "1_1") (pintype "passive"))
    )
    (net (code "101") (name "Net-(JP5-Pad3)") (class "Default")
      (node (ref "JP5") (pin "3") (pinfunction "3_3") (pintype "passive"))
      (node (ref "R47") (pin "2") (pinfunction "2_2") (pintype "passive"))
    )
    (net (code "102") (name "Net-(JP5-Pad4)") (class "Default")
      (node (ref "JP5") (pin "4") (pinfunction "4_4") (pintype "passive"))
      (node (ref "R48") (pin "2") (pinfunction "2_2") (pintype "passive"))
    )
    (net (code "103") (name "Net-(JP5-Pad5)") (class "Default")
      (node (ref "JP5") (pin "5") (pinfunction "5_5") (pintype "passive"))
      (node (ref "R50") (pin "2") (pinfunction "2_2") (pintype "passive"))
    )
    (net (code "104") (name "Net-(LED1-PadA)") (class "Default")
      (node (ref "LED1") (pin "A") (pinfunction "A_A") (pintype "passive"))
      (node (ref "R17") (pin "2") (pinfunction "2_2") (pintype "passive"))
    )
    (net (code "105") (name "Net-(LED2-PadA)") (class "Default")
      (node (ref "LED2") (pin "A") (pinfunction "A_A") (pintype "passive"))
      (node (ref "R20") (pin "2") (pinfunction "2_2") (pintype "passive"))
    )
    (net (code "106") (name "Net-(LED3-PadA)") (class "Default")
      (node (ref "LED3") (pin "A") (pinfunction "A_A") (pintype "passive"))
      (node (ref "R27") (pin "2") (pinfunction "2_2") (pintype "passive"))
    )
    (net (code "107") (name "Net-(LED4-PadA)") (class "Default")
      (node (ref "LED4") (pin "A") (pinfunction "A_A") (pintype "passive"))
      (node (ref "R42") (pin "2") (pinfunction "2_2") (pintype "passive"))
    )
    (net (code "108") (name "Net-(LED5-PadA)") (class "Default")
      (node (ref "LED5") (pin "A") (pinfunction "A_A") (pintype "passive"))
      (node (ref "R45") (pin "2") (pinfunction "2_2") (pintype "passive"))
    )
    (net (code "109") (name "Net-(LED6-PadA)") (class "Default")
      (node (ref "LED6") (pin "A") (pinfunction "A_A") (pintype "passive"))
      (node (ref "R49") (pin "2") (pinfunction "2_2") (pintype "passive"))
    )
    (net (code "110") (name "Net-(LED7-PadA)") (class "Default")
      (node (ref "LED7") (pin "A") (pinfunction "A_A") (pintype "passive"))
      (node (ref "R62") (pin "2") (pinfunction "2_2") (pintype "passive"))
    )
    (net (code "111") (name "Net-(Q1-G)") (class "Default")
      (node (ref "Q1") (pin "2") (pinfunction "G_2") (pintype "passive"))
      (node (ref "R92") (pin "2") (pinfunction "2_2") (pintype "passive"))
      (node (ref "R95") (pin "1") (pinfunction "1_1") (pintype "passive"))
    )
    (net (code "112") (name "Net-(Q2-G)") (class "Default")
      (node (ref "Q2") (pin "2") (pinfunction "G_2") (pintype "passive"))
      (node (ref "R93") (pin "2") (pinfunction "2_2") (pintype "passive"))
      (node (ref "R96") (pin "1") (pinfunction "1_1") (pintype "passive"))
    )
    (net (code "113") (name "Net-(Q3-G)") (class "Default")
      (node (ref "Q3") (pin "2") (pinfunction "G_2") (pintype "passive"))
      (node (ref "R94") (pin "2") (pinfunction "2_2") (pintype "passive"))
      (node (ref "R97") (pin "1") (pinfunction "1_1") (pintype "passive"))
    )
    (net (code "114") (name "Net-(Q4-G)") (class "Default")
      (node (ref "Q4") (pin "2") (pinfunction "G_2") (pintype "passive"))
      (node (ref "R101") (pin "1") (pinfunction "1_1") (pintype "passive"))
      (node (ref "R98") (pin "2") (pinfunction "2_2") (pintype "passive"))
    )
    (net (code "115") (name "Net-(Q5-G)") (class "Default")
      (node (ref "Q5") (pin "2") (pinfunction "G_2") (pintype "passive"))
      (node (ref "R102") (pin "1") (pinfunction "1_1") (pintype "passive"))
      (node (ref "R99") (pin "2") (pinfunction "2_2") (pintype "passive"))
    )
    (net (code "116") (name "Net-(Q6-G)") (class "Default")
      (node (ref "Q6") (pin "2") (pinfunction "G_2") (pintype "passive"))
      (node (ref "R100") (pin "2") (pinfunction "2_2") (pintype "passive"))
      (node (ref "R103") (pin "1") (pinfunction "1_1") (pintype "passive"))
    )
    (net (code "117") (name "Net-(Q7-G)") (class "Default")
      (node (ref "Q7") (pin "2") (pinfunction "G_2") (pintype "passive"))
      (node (ref "R104") (pin "2") (pinfunction "2_2") (pintype "passive"))
      (node (ref "R107") (pin "1") (pinfunction "1_1") (pintype "passive"))
    )
    (net (code "118") (name "Net-(Q8-G)") (class "Default")
      (node (ref "Q8") (pin "2") (pinfunction "G_2") (pintype "passive"))
      (node (ref "R105") (pin "2") (pinfunction "2_2") (pintype "passive"))
      (node (ref "R108") (pin "1") (pinfunction "1_1") (pintype "passive"))
    )
    (net (code "119") (name "Net-(Q9-G)") (class "Default")
      (node (ref "Q9") (pin "2") (pinfunction "G_2") (pintype "passive"))
      (node (ref "R106") (pin "2") (pinfunction "2_2") (pintype "passive"))
      (node (ref "R109") (pin "1") (pinfunction "1_1") (pintype "passive"))
    )
    (net (code "120") (name "Net-(Q10-G)") (class "Default")
      (node (ref "Q10") (pin "2") (pinfunction "G_2") (pintype "passive"))
      (node (ref "R110") (pin "2") (pinfunction "2_2") (pintype "passive"))
      (node (ref "R114") (pin "1") (pinfunction "1_1") (pintype "passive"))
    )
    (net (code "121") (name "Net-(Q11-G)") (class "Default")
      (node (ref "Q11") (pin "2") (pinfunction "G_2") (pintype "passive"))
      (node (ref "R111") (pin "2") (pinfunction "2_2") (pintype "passive"))
      (node (ref "R115") (pin "1") (pinfunction "1_1") (pintype "passive"))
    )
    (net (code "122") (name "Net-(Q12-G)") (class "Default")
      (node (ref "Q12") (pin "2") (pinfunction "G_2") (pintype "passive"))
      (node (ref "R112") (pin "2") (pinfunction "2_2") (pintype "passive"))
      (node (ref "R116") (pin "1") (pinfunction "1_1") (pintype "passive"))
    )
    (net (code "123") (name "Net-(U1-BOOT0)") (class "Default")
      (node (ref "R43") (pin "2") (pinfunction "2_2") (pintype "passive"))
      (node (ref "U1") (pin "94") (pinfunction "BOOT0_94") (pintype "passive"))
    )
    (net (code "124") (name "Net-(U1-OSC_IN)") (class "Default")
      (node (ref "C7") (pin "2") (pinfunction "2_2") (pintype "passive"))
      (node (ref "U1") (pin "12") (pinfunction "OSC_IN_12") (pintype "passive"))
      (node (ref "Y1") (pin "3") (pinfunction "OSC2_3") (pintype "passive"))
    )
    (net (code "125") (name "Net-(U1-OSC_OUT)") (class "Default")
      (node (ref "C8") (pin "2") (pinfunction "2_2") (pintype "passive"))
      (node (ref "U1") (pin "13") (pinfunction "OSC_OUT_13") (pintype "passive"))
      (node (ref "Y1") (pin "1") (pinfunction "OSC1_1") (pintype "passive"))
    )
    (net (code "126") (name "Net-(U1-VBAT)") (class "Default")
      (node (ref "R58") (pin "2") (pinfunction "2_2") (pintype "passive"))
      (node (ref "U1") (pin "6") (pinfunction "VBAT_6") (pintype "passive"))
    )
    (net (code "127") (name "Net-(U1-VREF+)") (class "Default")
      (node (ref "R57") (pin "2") (pinfunction "2_2") (pintype "passive"))
      (node (ref "U1") (pin "21") (pinfunction "VREF+_21") (pintype "passive"))
    )
    (net (code "128") (name "Net-(U1-VREF-)") (class "Default")
      (node (ref "R54") (pin "2") (pinfunction "2_2") (pintype "passive"))
      (node (ref "U1") (pin "20") (pinfunction "VREF-_20") (pintype "passive"))
    )
    (net (code "129") (name "Net-(U2-BS)") (class "Default")
      (node (ref "C18") (pin "1") (pinfunction "1_1") (pintype "passive"))
      (node (ref "U2") (pin "1") (pinfunction "BS_1") (pintype "passive"))
    )
    (net (code "130") (name "Net-(U2-FB)") (class "Default")
      (node (ref "C17") (pin "1") (pinfunction "1_1") (pintype "passive"))
      (node (ref "R59") (pin "1") (pinfunction "1_1") (pintype "passive"))
      (node (ref "R63") (pin "2") (pinfunction "2_2") (pintype "passive"))
      (node (ref "U2") (pin "3") (pinfunction "FB_3") (pintype "passive"))
    )
    (net (code "131") (name "Net-(U2-SW)") (class "Default")
      (node (ref "C18") (pin "2") (pinfunction "2_2") (pintype "passive"))
      (node (ref "L1") (pin "2") (pinfunction "2_2") (pintype "passive"))
      (node (ref "U2") (pin "6") (pinfunction "SW_6") (pintype "passive"))
    )
    (net (code "132") (name "Net-(U3-GND)") (class "Default")
      (node (ref "C22") (pin "1") (pinfunction "1_1") (pintype "passive"))
      (node (ref "C23") (pin "1") (pinfunction "1_1") (pintype "passive"))
      (node (ref "C24") (pin "1") (pinfunction "1_1") (pintype "passive"))
      (node (ref "C25") (pin "1") (pinfunction "1_1") (pintype "passive"))
      (node (ref "D8") (pin "A") (pinfunction "A_A") (pintype "passive"))
      (node (ref "D9") (pin "A") (pinfunction "A_A") (pintype "passive"))
      (node (ref "LED7") (pin "C") (pinfunction "C_C") (pintype "passive"))
      (node (ref "U3") (pin "2") (pinfunction "GND_2") (pintype "passive"))
    )
    (net (code "133") (name "Net-(U4-EN)") (class "Default")
      (node (ref "R65") (pin "1") (pinfunction "1_1") (pintype "passive"))
      (node (ref "U4") (pin "2") (pinfunction "EN_2") (pintype "passive"))
    )
    (net (code "134") (name "Net-(U4-FB)") (class "Default")
      (node (ref "R66") (pin "1") (pinfunction "1_1") (pintype "passive"))
      (node (ref "R67") (pin "1") (pinfunction "1_1") (pintype "passive"))
      (node (ref "U4") (pin "1") (pinfunction "FB_1") (pintype "passive"))
    )
    (net (code "135") (name "Net-(U4-IN)") (class "Default")
      (node (ref "D5") (pin "K") (pinfunction "K_K") (pintype "passive"))
      (node (ref "U4") (pin "4") (pinfunction "IN_4") (pintype "passive"))
      (node (ref "U4") (pin "5") (pinfunction "VCC_5") (pintype "passive"))
    )
    (net (code "136") (name "Net-(U5-HIN1)") (class "Default")
      (node (ref "R68") (pin "2") (pinfunction "2_2") (pintype "passive"))
      (node (ref "R70") (pin "2") (pinfunction "2_2") (pintype "passive"))
      (node (ref "U5") (pin "22") (pinfunction "HIN1_22") (pintype "passive"))
    )
    (net (code "137") (name "Net-(U5-HIN2)") (class "Default")
      (node (ref "R76") (pin "2") (pinfunction "2_2") (pintype "passive"))
      (node (ref "R78") (pin "2") (pinfunction "2_2") (pintype "passive"))
      (node (ref "U5") (pin "23") (pinfunction "HIN2_23") (pintype "passive"))
    )
    (net (code "138") (name "Net-(U5-HIN3)") (class "Default")
      (node (ref "R84") (pin "2") (pinfunction "2_2") (pintype "passive"))
      (node (ref "R86") (pin "2") (pinfunction "2_2") (pintype "passive"))
      (node (ref "U5") (pin "24") (pinfunction "HIN3_24") (pintype "passive"))
    )
    (net (code "139") (name "Net-(U5-LIN1)") (class "Default")
      (node (ref "R72") (pin "2") (pinfunction "2_2") (pintype "passive"))
      (node (ref "R74") (pin "2") (pinfunction "2_2") (pintype "passive"))
      (node (ref "U5") (pin "1") (pinfunction "LIN1_1") (pintype "passive"))
    )
    (net (code "140") (name "Net-(U5-LIN2)") (class "Default")
      (node (ref "R80") (pin "2") (pinfunction "2_2") (pintype "passive"))
      (node (ref "R82") (pin "2") (pinfunction "2_2") (pintype "passive"))
      (node (ref "U5") (pin "2") (pinfunction "LIN2_2") (pintype "passive"))
    )
    (net (code "141") (name "Net-(U5-LIN3)") (class "Default")
      (node (ref "R88") (pin "2") (pinfunction "2_2") (pintype "passive"))
      (node (ref "R90") (pin "2") (pinfunction "2_2") (pintype "passive"))
      (node (ref "U5") (pin "3") (pinfunction "LIN3_3") (pintype "passive"))
    )
    (net (code "142") (name "Net-(U5-VB1)") (class "Default")
      (node (ref "C32") (pin "2") (pinfunction "2_2") (pintype "passive"))
      (node (ref "D10") (pin "K") (pinfunction "K_K") (pintype "passive"))
      (node (ref "U5") (pin "20") (pinfunction "VB1_20") (pintype "passive"))
    )
    (net (code "143") (name "Net-(U5-VB2)") (class "Default")
      (node (ref "C34") (pin "2") (pinfunction "2_2") (pintype "passive"))
      (node (ref "D12") (pin "K") (pinfunction "K_K") (pintype "passive"))
      (node (ref "U5") (pin "17") (pinfunction "VB2_17") (pintype "passive"))
    )
    (net (code "144") (name "Net-(U5-VB3)") (class "Default")
      (node (ref "C36") (pin "2") (pinfunction "2_2") (pintype "passive"))
      (node (ref "D14") (pin "K") (pinfunction "K_K") (pintype "passive"))
      (node (ref "U5") (pin "14") (pinfunction "VB3_14") (pintype "passive"))
    )
    (net (code "145") (name "Net-(U6-HIN1)") (class "Default")
      (node (ref "R69") (pin "2") (pinfunction "2_2") (pintype "passive"))
      (node (ref "R71") (pin "2") (pinfunction "2_2") (pintype "passive"))
      (node (ref "U6") (pin "22") (pinfunction "HIN1_22") (pintype "passive"))
    )
    (net (code "146") (name "Net-(U6-HIN2)") (class "Default")
      (node (ref "R77") (pin "2") (pinfunction "2_2") (pintype "passive"))
      (node (ref "R79") (pin "2") (pinfunction "2_2") (pintype "passive"))
      (node (ref "U6") (pin "23") (pinfunction "HIN2_23") (pintype "passive"))
    )
    (net (code "147") (name "Net-(U6-HIN3)") (class "Default")
      (node (ref "R85") (pin "2") (pinfunction "2_2") (pintype "passive"))
      (node (ref "R87") (pin "2") (pinfunction "2_2") (pintype "passive"))
      (node (ref "U6") (pin "24") (pinfunction "HIN3_24") (pintype "passive"))
    )
    (net (code "148") (name "Net-(U6-LIN1)") (class "Default")
      (node (ref "R73") (pin "2") (pinfunction "2_2") (pintype "passive"))
      (node (ref "R75") (pin "2") (pinfunction "2_2") (pintype "passive"))
      (node (ref "U6") (pin "1") (pinfunction "LIN1_1") (pintype "passive"))
    )
    (net (code "149") (name "Net-(U6-LIN2)") (class "Default")
      (node (ref "R81") (pin "2") (pinfunction "2_2") (pintype "passive"))
      (node (ref "R83") (pin "2") (pinfunction "2_2") (pintype "passive"))
      (node (ref "U6") (pin "2") (pinfunction "LIN2_2") (pintype "passive"))
    )
    (net (code "150") (name "Net-(U6-LIN3)") (class "Default")
      (node (ref "R89") (pin "2") (pinfunction "2_2") (pintype "passive"))
      (node (ref "R91") (pin "2") (pinfunction "2_2") (pintype "passive"))
      (node (ref "U6") (pin "3") (pinfunction "LIN3_3") (pintype "passive"))
    )
    (net (code "151") (name "Net-(U6-VB1)") (class "Default")
      (node (ref "C33") (pin "2") (pinfunction "2_2") (pintype "passive"))
      (node (ref "D11") (pin "K") (pinfunction "K_K") (pintype "passive"))
      (node (ref "U6") (pin "20") (pinfunction "VB1_20") (pintype "passive"))
    )
    (net (code "152") (name "Net-(U6-VB2)") (class "Default")
      (node (ref "C35") (pin "2") (pinfunction "2_2") (pintype "passive"))
      (node (ref "D13") (pin "K") (pinfunction "K_K") (pintype "passive"))
      (node (ref "U6") (pin "17") (pinfunction "VB2_17") (pintype "passive"))
    )
    (net (code "153") (name "Net-(U6-VB3)") (class "Default")
      (node (ref "C37") (pin "2") (pinfunction "2_2") (pintype "passive"))
      (node (ref "D15") (pin "K") (pinfunction "K_K") (pintype "passive"))
      (node (ref "U6") (pin "14") (pinfunction "VB3_14") (pintype "passive"))
    )
    (net (code "154") (name "VBAT") (class "Default")
      (node (ref "D5") (pin "A") (pinfunction "A_A") (pintype "passive"))
      (node (ref "D6") (pin "1") (pinfunction "1_1") (pintype "passive"))
      (node (ref "D7") (pin "1") (pinfunction "1_1") (pintype "passive"))
      (node (ref "E1") (pin "1") (pinfunction "A_1") (pintype "passive"))
      (node (ref "E2") (pin "1") (pinfunction "A_1") (pintype "passive"))
      (node (ref "JP6") (pin "2") (pinfunction "2_2") (pintype "passive"))
      (node (ref "Q1") (pin "1") (pinfunction "D_1") (pintype "passive"))
      (node (ref "Q2") (pin "1") (pinfunction "D_1") (pintype "passive"))
      (node (ref "Q3") (pin "1") (pinfunction "D_1") (pintype "passive"))
      (node (ref "Q4") (pin "1") (pinfunction "D_1") (pintype "passive"))
      (node (ref "Q5") (pin "1") (pinfunction "D_1") (pintype "passive"))
      (node (ref "Q6") (pin "1") (pinfunction "D_1") (pintype "passive"))
      (node (ref "R60") (pin "2") (pinfunction "2_2") (pintype "passive"))
      (node (ref "R65") (pin "2") (pinfunction "2_2") (pintype "passive"))
      (node (ref "R66") (pin "2") (pinfunction "2_2") (pintype "passive"))
    )
    (net (code "155") (name "unconnected-(C28-Pad2)") (class "Default")
      (node (ref "C28") (pin "2") (pinfunction "2_2") (pintype "passive"))
    )
    (net (code "156") (name "unconnected-(C29-Pad2)") (class "Default")
      (node (ref "C29") (pin "2") (pinfunction "2_2") (pintype "passive"))
    )
    (net (code "157") (name "unconnected-(JP1-Pad6)") (class "Default")
      (node (ref "JP1") (pin "6") (pinfunction "6_6") (pintype "passive+no_connect"))
    )
    (net (code "158") (name "unconnected-(JP1-Pad8)") (class "Default")
      (node (ref "JP1") (pin "8") (pinfunction "8_8") (pintype "passive+no_connect"))
    )
    (net (code "159") (name "unconnected-(U1-NC-Pad73)") (class "Default")
      (node (ref "U1") (pin "73") (pinfunction "NC_73") (pintype "passive+no_connect"))
    )
    (net (code "160") (name "unconnected-(U1-OSC32IN{slash}PC14-Pad8)") (class "Default")
      (node (ref "U1") (pin "8") (pinfunction "OSC32IN/PC14_8") (pintype "passive+no_connect"))
    )
    (net (code "161") (name "unconnected-(U1-OSC32OUT{slash}PC15-Pad9)") (class "Default")
      (node (ref "U1") (pin "9") (pinfunction "OSC32OUT/PC15_9") (pintype "passive+no_connect"))
    )
    (net (code "162") (name "unconnected-(U1-PA11{slash}USB1DM-Pad70)") (class "Default")
      (node (ref "U1") (pin "70") (pinfunction "PA11/USB1DM_70") (pintype "passive+no_connect"))
    )
    (net (code "163") (name "unconnected-(U1-PA12{slash}USB1DP-Pad71)") (class "Default")
      (node (ref "U1") (pin "71") (pinfunction "PA12/USB1DP_71") (pintype "passive+no_connect"))
    )
    (net (code "164") (name "unconnected-(U1-PA15-Pad77)") (class "Default")
      (node (ref "U1") (pin "77") (pinfunction "PA15_77") (pintype "passive+no_connect"))
    )
    (net (code "165") (name "unconnected-(U1-PB2{slash}BOOT1-Pad37)") (class "Default")
      (node (ref "U1") (pin "37") (pinfunction "PB2/BOOT1_37") (pintype "passive"))
    )
    (net (code "166") (name "unconnected-(U1-PB4-Pad90)") (class "Default")
      (node (ref "U1") (pin "90") (pinfunction "PB4_90") (pintype "passive+no_connect"))
    )
    (net (code "167") (name "unconnected-(U1-PB5-Pad91)") (class "Default")
      (node (ref "U1") (pin "91") (pinfunction "PB5_91") (pintype "passive+no_connect"))
    )
    (net (code "168") (name "unconnected-(U1-PB9-Pad96)") (class "Default")
      (node (ref "U1") (pin "96") (pinfunction "PB9_96") (pintype "passive+no_connect"))
    )
    (net (code "169") (name "unconnected-(U1-PB12-Pad51)") (class "Default")
      (node (ref "U1") (pin "51") (pinfunction "PB12_51") (pintype "passive+no_connect"))
    )
    (net (code "170") (name "unconnected-(U1-PB13-Pad52)") (class "Default")
      (node (ref "U1") (pin "52") (pinfunction "PB13_52") (pintype "passive+no_connect"))
    )
    (net (code "171") (name "unconnected-(U1-PC10-Pad78)") (class "Default")
      (node (ref "U1") (pin "78") (pinfunction "PC10_78") (pintype "passive+no_connect"))
    )
    (net (code "172") (name "unconnected-(U1-PC12-Pad80)") (class "Default")
      (node (ref "U1") (pin "80") (pinfunction "PC12_80") (pintype "passive+no_connect"))
    )
    (net (code "173") (name "unconnected-(U1-PD0-Pad81)") (class "Default")
      (node (ref "U1") (pin "81") (pinfunction "PD0_81") (pintype "passive+no_connect"))
    )
    (net (code "174") (name "unconnected-(U1-PD1-Pad82)") (class "Default")
      (node (ref "U1") (pin "82") (pinfunction "PD1_82") (pintype "passive+no_connect"))
    )
    (net (code "175") (name "unconnected-(U1-PD2-Pad83)") (class "Default")
      (node (ref "U1") (pin "83") (pinfunction "PD2_83") (pintype "passive+no_connect"))
    )
    (net (code "176") (name "unconnected-(U1-PD7-Pad88)") (class "Default")
      (node (ref "U1") (pin "88") (pinfunction "PD7_88") (pintype "passive+no_connect"))
    )
    (net (code "177") (name "unconnected-(U1-PD15-Pad62)") (class "Default")
      (node (ref "U1") (pin "62") (pinfunction "PD15_62") (pintype "passive+no_connect"))
    )
    (net (code "178") (name "unconnected-(U1-PE6-Pad5)") (class "Default")
      (node (ref "U1") (pin "5") (pinfunction "PE6_5") (pintype "passive+no_connect"))
    )
    (net (code "179") (name "unconnected-(U1-PE13-Pad44)") (class "Default")
      (node (ref "U1") (pin "44") (pinfunction "PE13_44") (pintype "passive+no_connect"))
    )
    (net (code "180") (name "unconnected-(U1-PE14-Pad45)") (class "Default")
      (node (ref "U1") (pin "45") (pinfunction "PE14_45") (pintype "passive+no_connect"))
    )
    (net (code "181") (name "unconnected-(U1-PE15-Pad46)") (class "Default")
      (node (ref "U1") (pin "46") (pinfunction "PE15_46") (pintype "passive+no_connect"))
    )
    (net (code "182") (name "unconnected-(U1-TAMPER-RTC{slash}PC13-Pad7)") (class "Default")
      (node (ref "U1") (pin "7") (pinfunction "TAMPER-RTC/PC13_7") (pintype "passive+no_connect"))
    )
    (net (code "183") (name "unconnected-(U3-NC-Pad4)") (class "Default")
      (node (ref "U3") (pin "4") (pinfunction "NC_4") (pintype "passive+no_connect"))
    )
    (net (code "184") (name "unconnected-(U5-NC-Pad5)") (class "Default")
      (node (ref "U5") (pin "5") (pinfunction "NC_5") (pintype "passive+no_connect"))
    )
    (net (code "185") (name "unconnected-(U5-NC-Pad7)") (class "Default")
      (node (ref "U5") (pin "7") (pinfunction "NC_7") (pintype "passive+no_connect"))
    )
    (net (code "186") (name "unconnected-(U5-NC-Pad8)") (class "Default")
      (node (ref "U5") (pin "8") (pinfunction "NC_8") (pintype "passive+no_connect"))
    )
    (net (code "187") (name "unconnected-(U5-NC-Pad21)") (class "Default")
      (node (ref "U5") (pin "21") (pinfunction "NC_21") (pintype "passive+no_connect"))
    )
    (net (code "188") (name "unconnected-(U6-NC-Pad5)") (class "Default")
      (node (ref "U6") (pin "5") (pinfunction "NC_5") (pintype "passive+no_connect"))
    )
    (net (code "189") (name "unconnected-(U6-NC-Pad7)") (class "Default")
      (node (ref "U6") (pin "7") (pinfunction "NC_7") (pintype "passive+no_connect"))
    )
    (net (code "190") (name "unconnected-(U6-NC-Pad8)") (class "Default")
      (node (ref "U6") (pin "8") (pinfunction "NC_8") (pintype "passive+no_connect"))
    )
    (net (code "191") (name "unconnected-(U6-NC-Pad21)") (class "Default")
      (node (ref "U6") (pin "21") (pinfunction "NC_21") (pintype "passive+no_connect"))
    )
  )
)
